# homeboard14.net
KiCad netlist of a schematic drawn in EAGLE
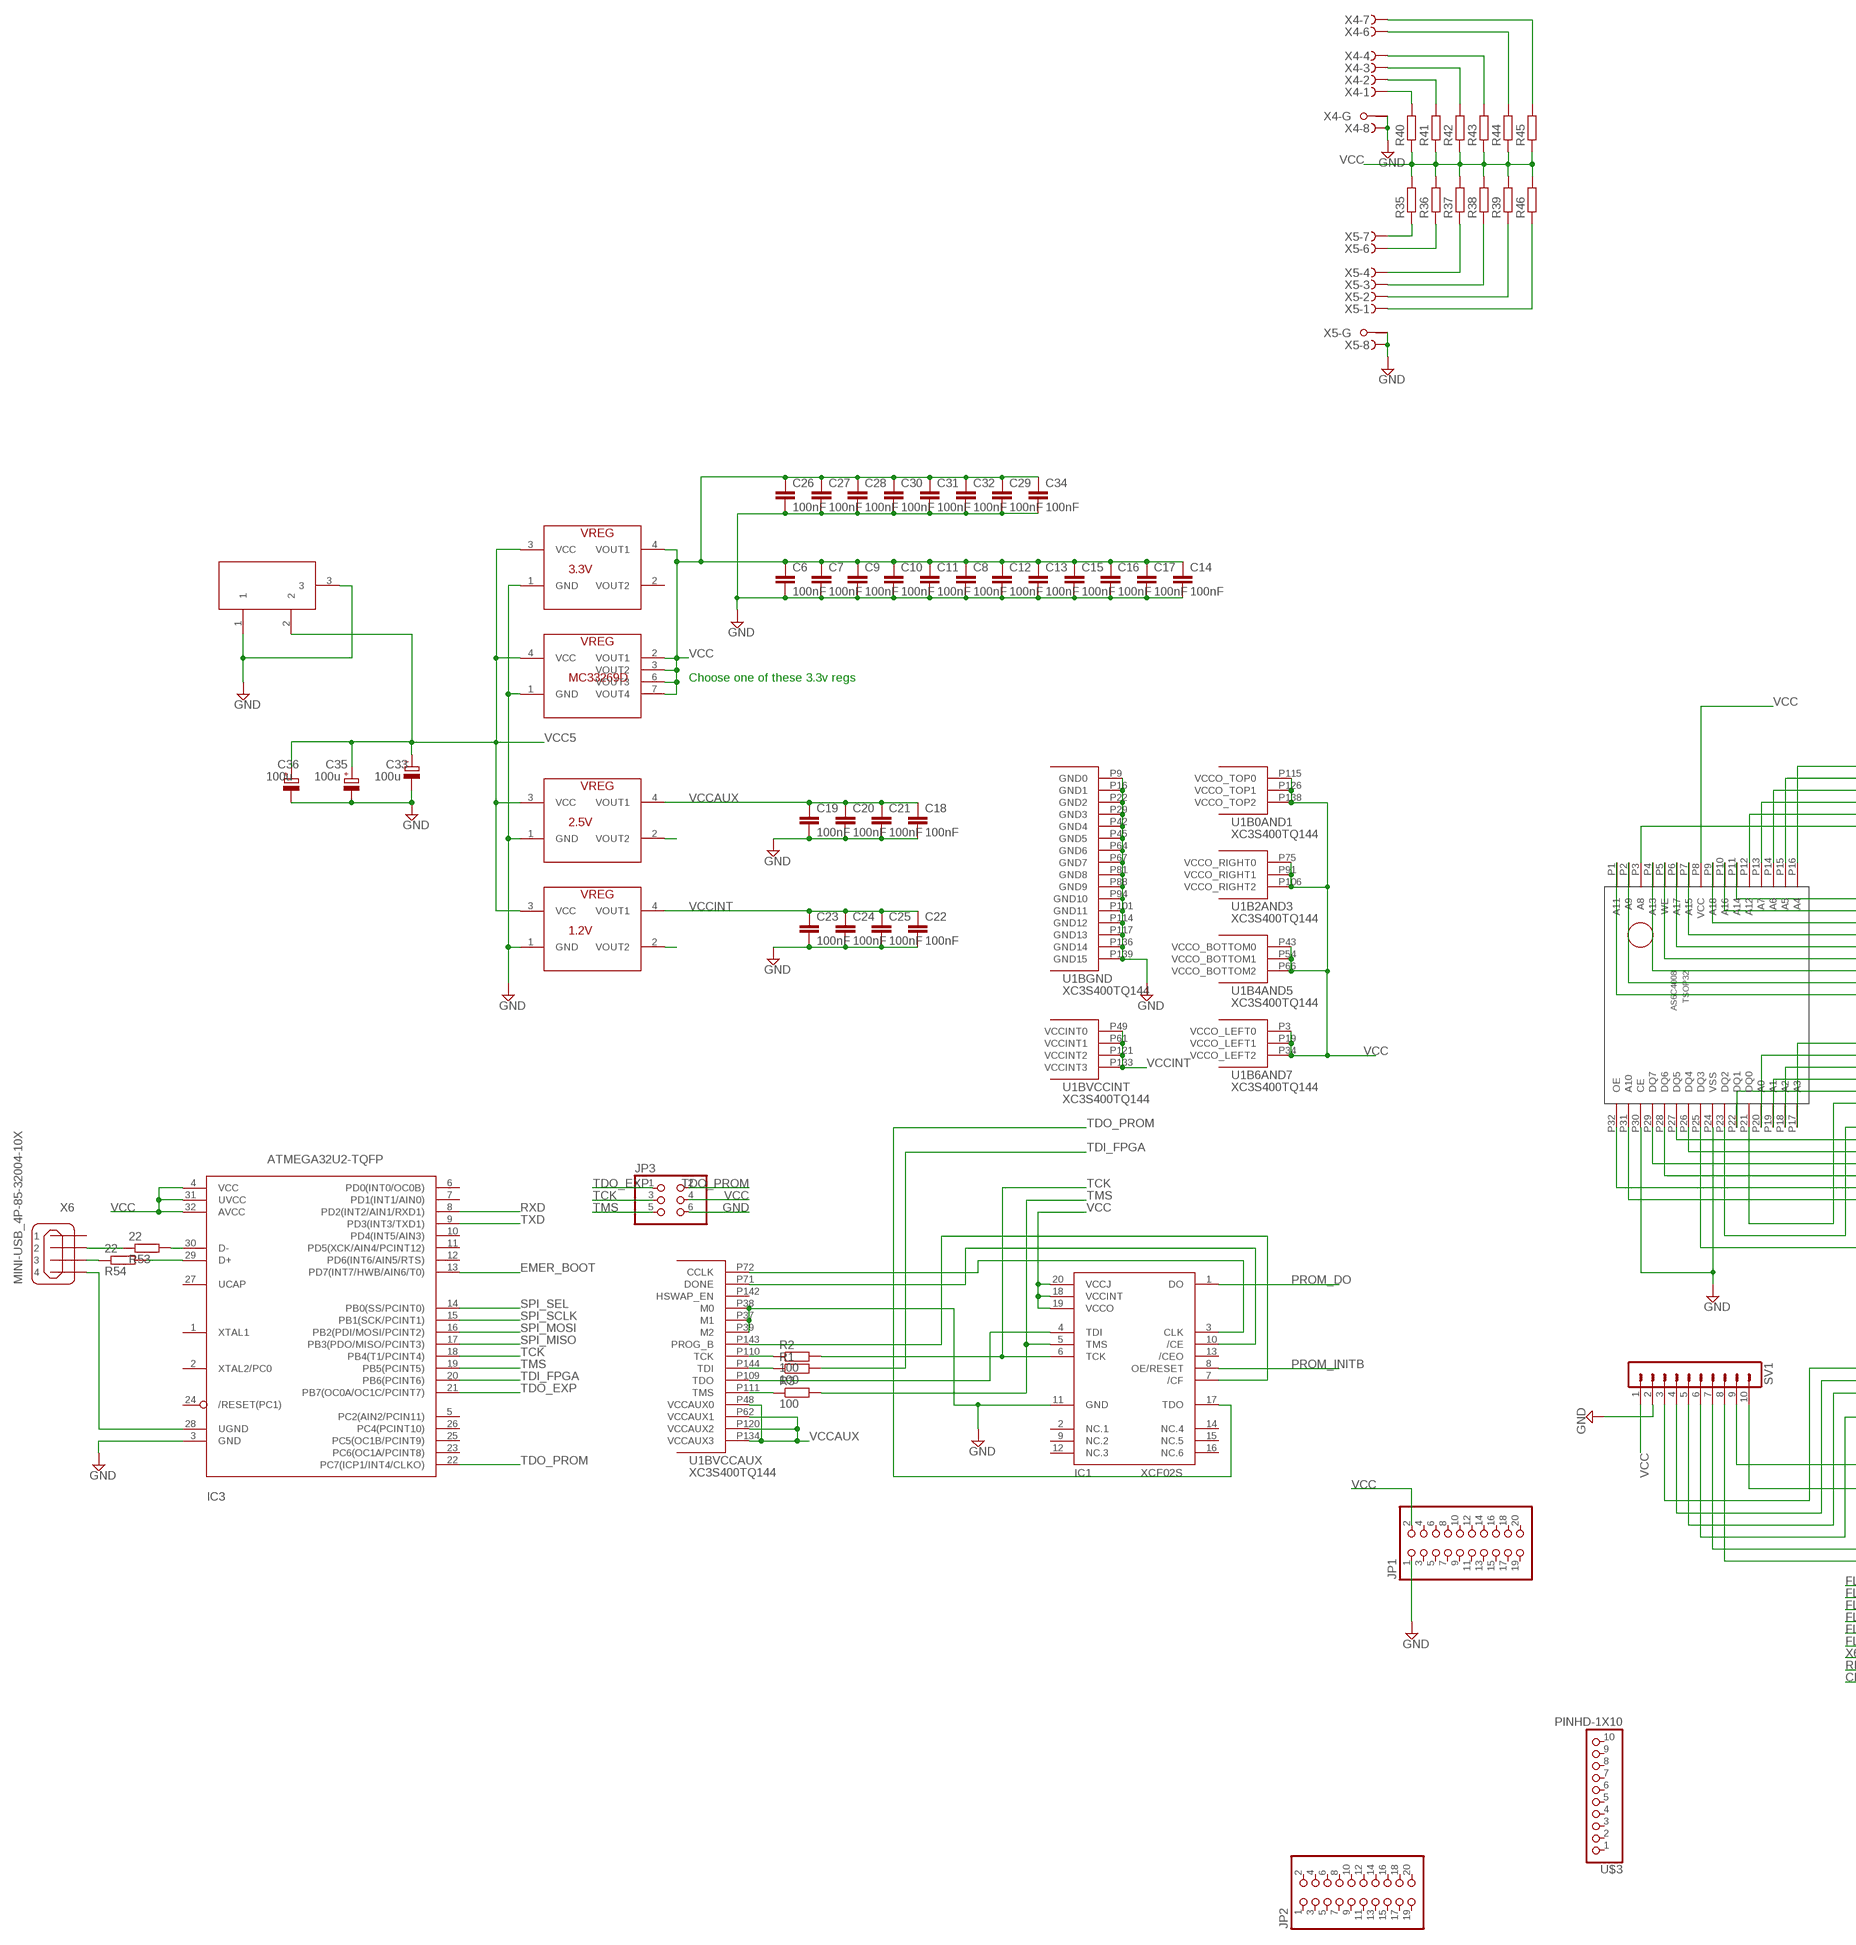
[diagram p0: schematic, sheet 1, part 1 of 3]
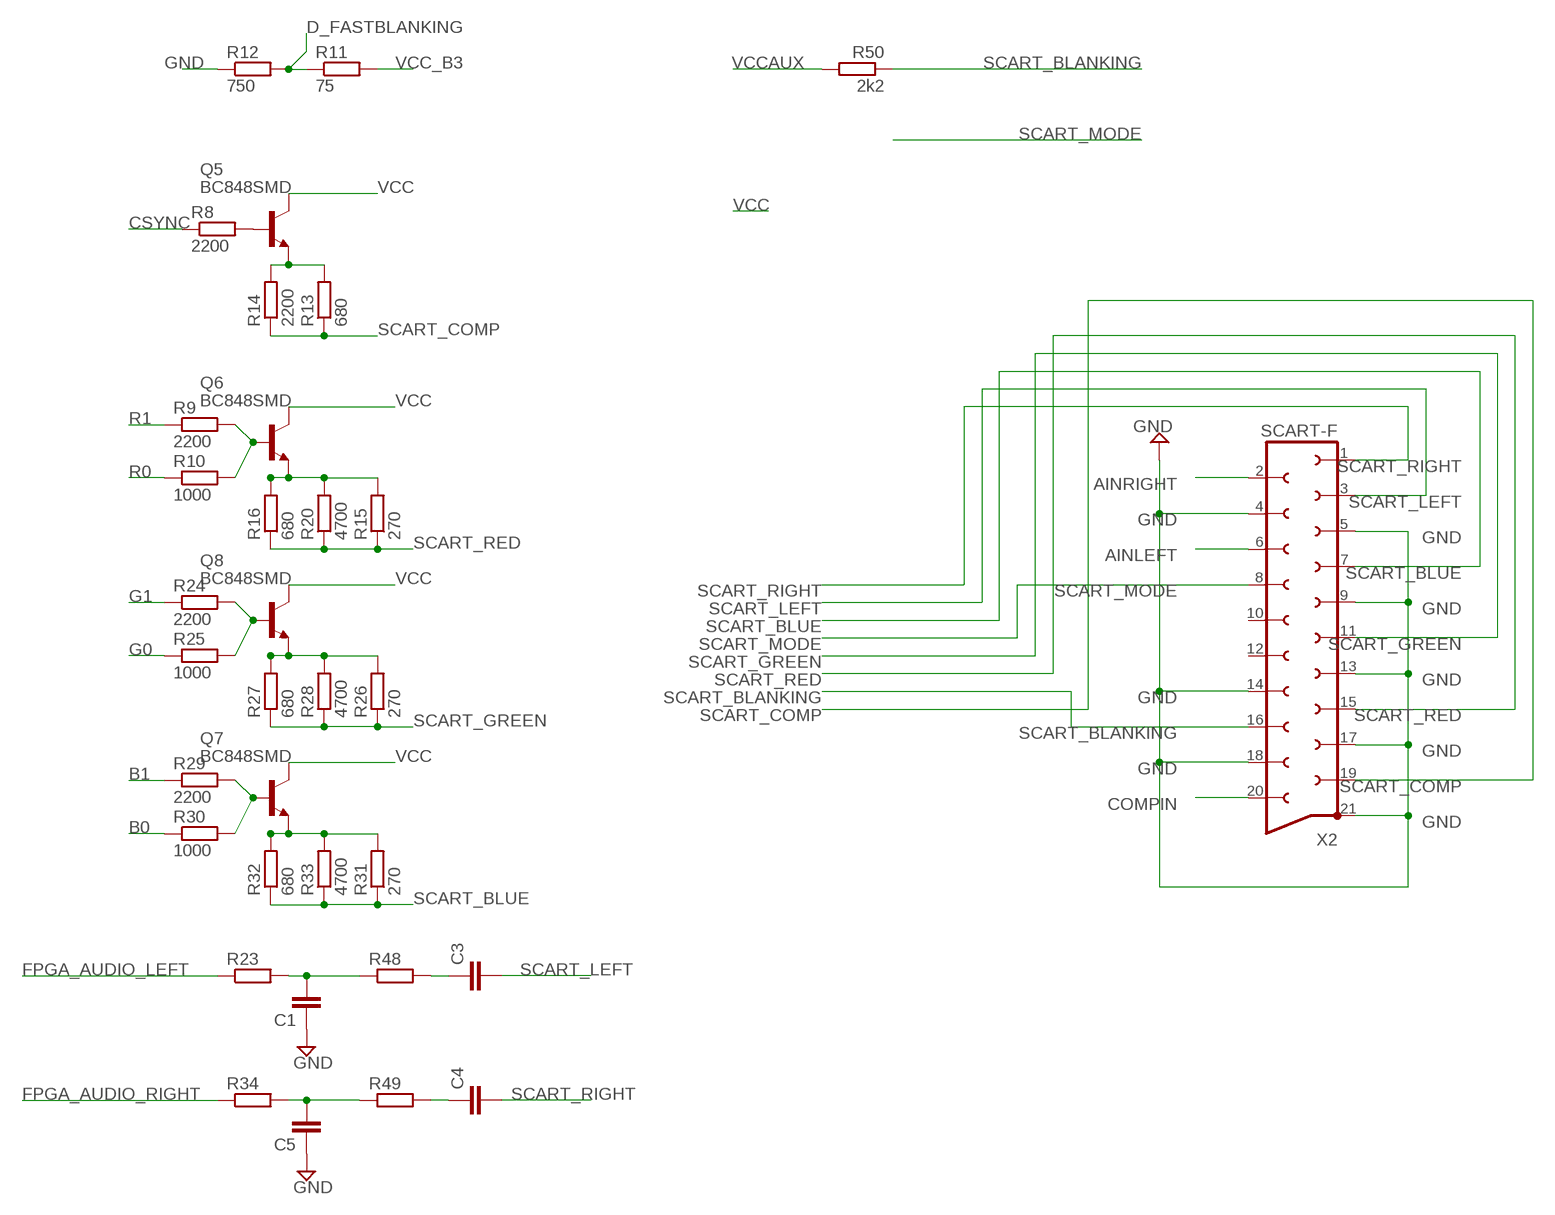
[diagram p1: schematic, sheet 1, part 2 of 3]
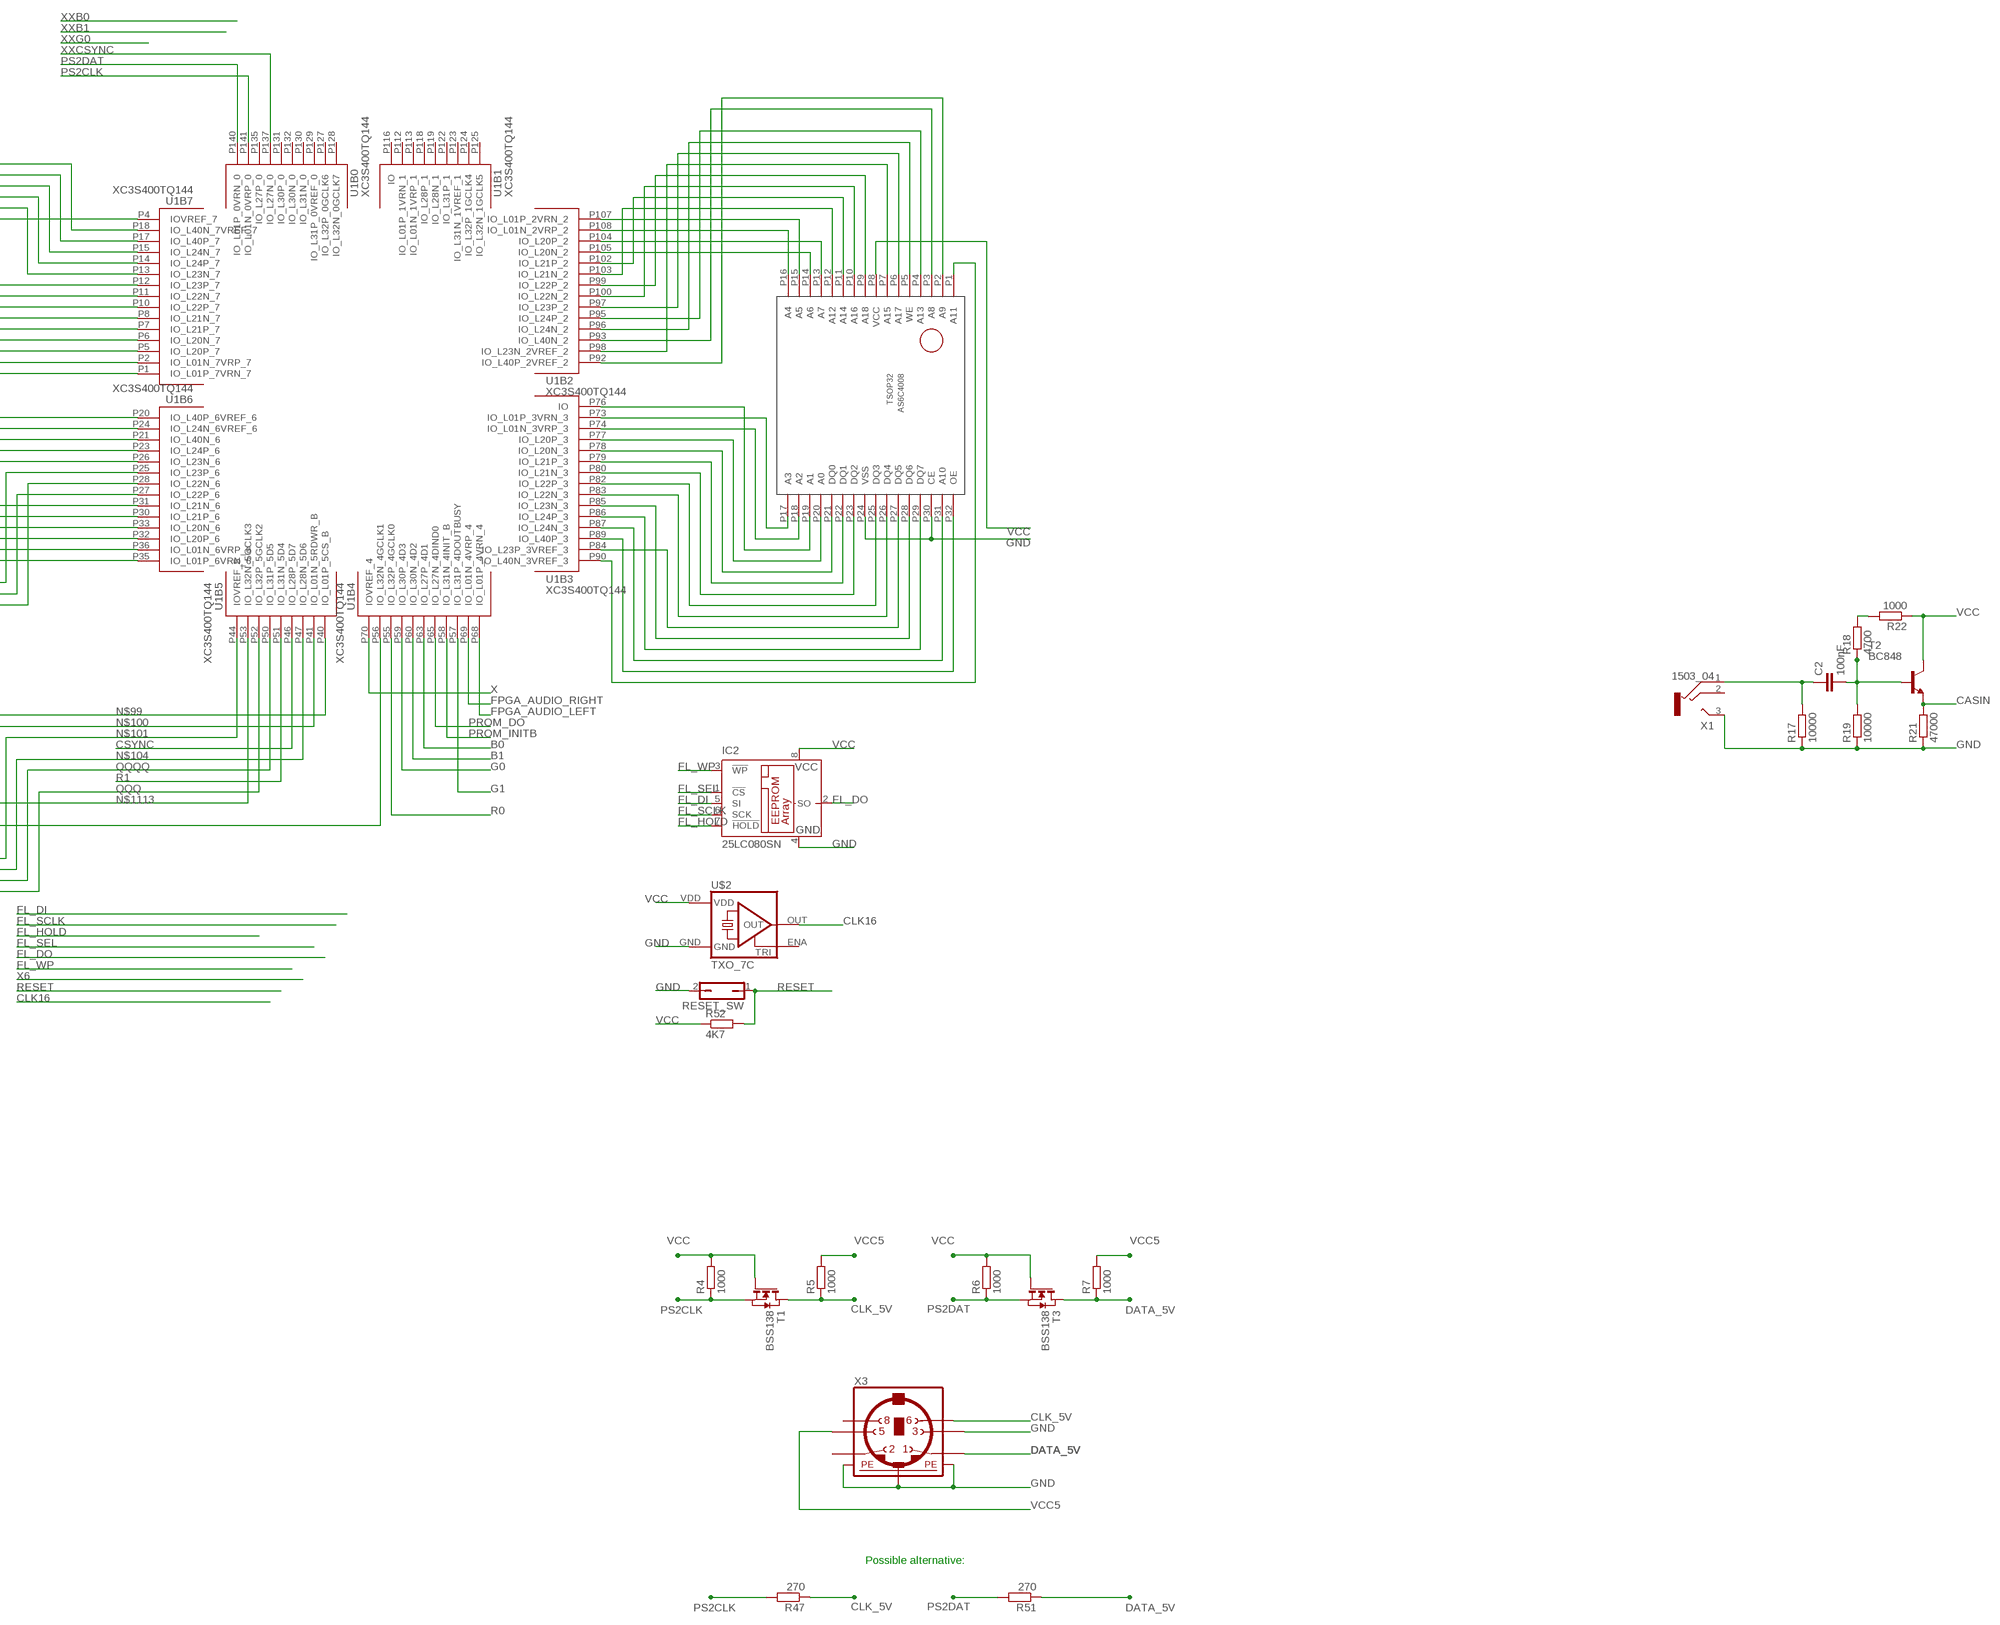
[diagram p2: schematic, sheet 1, part 3 of 3]

(export (version "E")
  (design (tool "Eeschema 10.0.6"))
  (components
    (comp (ref "C1")
      (value "C-EUC0603")
      (footprint "eagle-import:C0603")
      (libsource (lib "eagle-import") (part "resistor_C-EUC0603"))
    )
    (comp (ref "C2")
      (value "100nF")
      (footprint "eagle-import:C0603")
      (libsource (lib "eagle-import") (part "resistor_C-EUC0603"))
    )
    (comp (ref "C3")
      (value "C-EUC0603")
      (footprint "eagle-import:C0603")
      (libsource (lib "eagle-import") (part "resistor_C-EUC0603"))
    )
    (comp (ref "C4")
      (value "C-EUC0603")
      (footprint "eagle-import:C0603")
      (libsource (lib "eagle-import") (part "resistor_C-EUC0603"))
    )
    (comp (ref "C5")
      (value "C-EUC0603")
      (footprint "eagle-import:C0603")
      (libsource (lib "eagle-import") (part "resistor_C-EUC0603"))
    )
    (comp (ref "C6")
      (value "100nF")
      (footprint "eagle-import:C0603")
      (libsource (lib "eagle-import") (part "C-EUC0603"))
    )
    (comp (ref "C7")
      (value "100nF")
      (footprint "eagle-import:C0603")
      (libsource (lib "eagle-import") (part "C-EUC0603"))
    )
    (comp (ref "C8")
      (value "100nF")
      (footprint "eagle-import:C0603")
      (libsource (lib "eagle-import") (part "C-EUC0603"))
    )
    (comp (ref "C9")
      (value "100nF")
      (footprint "eagle-import:C0603")
      (libsource (lib "eagle-import") (part "C-EUC0603"))
    )
    (comp (ref "C10")
      (value "100nF")
      (footprint "eagle-import:C0603")
      (libsource (lib "eagle-import") (part "C-EUC0603"))
    )
    (comp (ref "C11")
      (value "100nF")
      (footprint "eagle-import:C0603")
      (libsource (lib "eagle-import") (part "C-EUC0603"))
    )
    (comp (ref "C12")
      (value "100nF")
      (footprint "eagle-import:C0603")
      (libsource (lib "eagle-import") (part "C-EUC0603"))
    )
    (comp (ref "C13")
      (value "100nF")
      (footprint "eagle-import:C0603")
      (libsource (lib "eagle-import") (part "C-EUC0603"))
    )
    (comp (ref "C14")
      (value "100nF")
      (footprint "eagle-import:C0603")
      (libsource (lib "eagle-import") (part "C-EUC0603"))
    )
    (comp (ref "C15")
      (value "100nF")
      (footprint "eagle-import:C0603")
      (libsource (lib "eagle-import") (part "C-EUC0603"))
    )
    (comp (ref "C16")
      (value "100nF")
      (footprint "eagle-import:C0603")
      (libsource (lib "eagle-import") (part "C-EUC0603"))
    )
    (comp (ref "C17")
      (value "100nF")
      (footprint "eagle-import:C0603")
      (libsource (lib "eagle-import") (part "C-EUC0603"))
    )
    (comp (ref "C18")
      (value "100nF")
      (footprint "eagle-import:C0603")
      (libsource (lib "eagle-import") (part "C-EUC0603"))
    )
    (comp (ref "C19")
      (value "100nF")
      (footprint "eagle-import:C0603")
      (libsource (lib "eagle-import") (part "C-EUC0603"))
    )
    (comp (ref "C20")
      (value "100nF")
      (footprint "eagle-import:C0603")
      (libsource (lib "eagle-import") (part "C-EUC0603"))
    )
    (comp (ref "C21")
      (value "100nF")
      (footprint "eagle-import:C0603")
      (libsource (lib "eagle-import") (part "C-EUC0603"))
    )
    (comp (ref "C22")
      (value "100nF")
      (footprint "eagle-import:C0603")
      (libsource (lib "eagle-import") (part "C-EUC0603"))
    )
    (comp (ref "C23")
      (value "100nF")
      (footprint "eagle-import:C0603")
      (libsource (lib "eagle-import") (part "C-EUC0603"))
    )
    (comp (ref "C24")
      (value "100nF")
      (footprint "eagle-import:C0603")
      (libsource (lib "eagle-import") (part "C-EUC0603"))
    )
    (comp (ref "C25")
      (value "100nF")
      (footprint "eagle-import:C0603")
      (libsource (lib "eagle-import") (part "C-EUC0603"))
    )
    (comp (ref "C26")
      (value "100nF")
      (footprint "eagle-import:C0603")
      (libsource (lib "eagle-import") (part "C-EUC0603"))
    )
    (comp (ref "C27")
      (value "100nF")
      (footprint "eagle-import:C0603")
      (libsource (lib "eagle-import") (part "C-EUC0603"))
    )
    (comp (ref "C28")
      (value "100nF")
      (footprint "eagle-import:C0603")
      (libsource (lib "eagle-import") (part "C-EUC0603"))
    )
    (comp (ref "C29")
      (value "100nF")
      (footprint "eagle-import:C0603")
      (libsource (lib "eagle-import") (part "C-EUC0603"))
    )
    (comp (ref "C30")
      (value "100nF")
      (footprint "eagle-import:C0603")
      (libsource (lib "eagle-import") (part "C-EUC0603"))
    )
    (comp (ref "C31")
      (value "100nF")
      (footprint "eagle-import:C0603")
      (libsource (lib "eagle-import") (part "C-EUC0603"))
    )
    (comp (ref "C32")
      (value "100nF")
      (footprint "eagle-import:C0603")
      (libsource (lib "eagle-import") (part "C-EUC0603"))
    )
    (comp (ref "C33")
      (value "100u")
      (footprint "eagle-import:PANASONIC_D")
      (libsource (lib "eagle-import") (part "CPOL-EUD"))
    )
    (comp (ref "C34")
      (value "100nF")
      (footprint "eagle-import:C0603")
      (libsource (lib "eagle-import") (part "C-EUC0603"))
    )
    (comp (ref "C35")
      (value "100u")
      (footprint "eagle-import:PANASONIC_D")
      (libsource (lib "eagle-import") (part "CPOL-EUD"))
    )
    (comp (ref "C36")
      (value "100u")
      (footprint "eagle-import:PANASONIC_D")
      (libsource (lib "eagle-import") (part "CPOL-EUD"))
    )
    (comp (ref "IC1")
      (value "XCF02S")
      (footprint "eagle-import:VO20")
      (libsource (lib "eagle-import") (part "XCF02S"))
    )
    (comp (ref "IC2")
      (value "25LC080SN")
      (footprint "eagle-import:SO-08")
      (fields (field (name "MF") "MICROCHIP") (field (name "MPN") "25LC080/SN"))
      (libsource (lib "eagle-import") (part "25SNLC080"))
    )
    (comp (ref "IC3")
      (value "ATMEGA32U2-TQFP")
      (footprint "eagle-import:TQFP32-08")
      (libsource (lib "eagle-import") (part "ATMEGA32U2-TQFP"))
    )
    (comp (ref "JP1")
      (value "PINHD-2X10")
      (footprint "eagle-import:2X10")
      (libsource (lib "eagle-import") (part "PINHD-2X10"))
    )
    (comp (ref "JP2")
      (value "PINHD-2X10")
      (footprint "eagle-import:2X10")
      (libsource (lib "eagle-import") (part "PINHD-2X10"))
    )
    (comp (ref "JP3")
      (value "PINHD-2X3")
      (footprint "eagle-import:2X03")
      (libsource (lib "eagle-import") (part "PINHD-2X3"))
    )
    (comp (ref "Q5")
      (value "BC848SMD")
      (footprint "eagle-import:SOT23")
      (libsource (lib "eagle-import") (part "BC848SMD"))
    )
    (comp (ref "Q6")
      (value "BC848SMD")
      (footprint "eagle-import:SOT23")
      (libsource (lib "eagle-import") (part "BC848SMD"))
    )
    (comp (ref "Q7")
      (value "BC848SMD")
      (footprint "eagle-import:SOT23")
      (libsource (lib "eagle-import") (part "BC848SMD"))
    )
    (comp (ref "Q8")
      (value "BC848SMD")
      (footprint "eagle-import:SOT23")
      (libsource (lib "eagle-import") (part "BC848SMD"))
    )
    (comp (ref "R1")
      (value "100")
      (footprint "eagle-import:R0805")
      (libsource (lib "eagle-import") (part "R-EU_R0805"))
    )
    (comp (ref "R2")
      (value "100")
      (footprint "eagle-import:R0805")
      (libsource (lib "eagle-import") (part "R-EU_R0805"))
    )
    (comp (ref "R3")
      (value "100")
      (footprint "eagle-import:R0805")
      (libsource (lib "eagle-import") (part "R-EU_R0805"))
    )
    (comp (ref "R4")
      (value "1000")
      (footprint "eagle-import:R0805")
      (libsource (lib "eagle-import") (part "R-EU_R0805"))
    )
    (comp (ref "R5")
      (value "1000")
      (footprint "eagle-import:R0805")
      (libsource (lib "eagle-import") (part "R-EU_R0805"))
    )
    (comp (ref "R6")
      (value "1000")
      (footprint "eagle-import:R0805")
      (libsource (lib "eagle-import") (part "R-EU_R0805"))
    )
    (comp (ref "R7")
      (value "1000")
      (footprint "eagle-import:R0805")
      (libsource (lib "eagle-import") (part "R-EU_R0805"))
    )
    (comp (ref "R8")
      (value "2200")
      (footprint "eagle-import:R0805")
      (libsource (lib "eagle-import") (part "R-EU_R0805"))
    )
    (comp (ref "R9")
      (value "2200")
      (footprint "eagle-import:R0805")
      (libsource (lib "eagle-import") (part "R-EU_R0805"))
    )
    (comp (ref "R10")
      (value "1000")
      (footprint "eagle-import:R0805")
      (libsource (lib "eagle-import") (part "R-EU_R0805"))
    )
    (comp (ref "R11")
      (value "75")
      (footprint "eagle-import:R0805")
      (libsource (lib "eagle-import") (part "R-EU_R0805"))
    )
    (comp (ref "R12")
      (value "750")
      (footprint "eagle-import:R0805")
      (libsource (lib "eagle-import") (part "R-EU_R0805"))
    )
    (comp (ref "R13")
      (value "680")
      (footprint "eagle-import:R0805")
      (libsource (lib "eagle-import") (part "R-EU_R0805"))
    )
    (comp (ref "R14")
      (value "2200")
      (footprint "eagle-import:R0805")
      (libsource (lib "eagle-import") (part "R-EU_R0805"))
    )
    (comp (ref "R15")
      (value "270")
      (footprint "eagle-import:R0805")
      (libsource (lib "eagle-import") (part "R-EU_R0805"))
    )
    (comp (ref "R16")
      (value "680")
      (footprint "eagle-import:R0805")
      (libsource (lib "eagle-import") (part "R-EU_R0805"))
    )
    (comp (ref "R17")
      (value "10000")
      (footprint "eagle-import:R0805")
      (libsource (lib "eagle-import") (part "R-EU_R0805"))
    )
    (comp (ref "R18")
      (value "4700")
      (footprint "eagle-import:R0805")
      (libsource (lib "eagle-import") (part "R-EU_R0805"))
    )
    (comp (ref "R19")
      (value "10000")
      (footprint "eagle-import:R0805")
      (libsource (lib "eagle-import") (part "R-EU_R0805"))
    )
    (comp (ref "R20")
      (value "4700")
      (footprint "eagle-import:R0805")
      (libsource (lib "eagle-import") (part "R-EU_R0805"))
    )
    (comp (ref "R21")
      (value "47000")
      (footprint "eagle-import:R0805")
      (libsource (lib "eagle-import") (part "R-EU_R0805"))
    )
    (comp (ref "R22")
      (value "1000")
      (footprint "eagle-import:R0805")
      (libsource (lib "eagle-import") (part "R-EU_R0805"))
    )
    (comp (ref "R23")
      (value "R-EU_M0805")
      (footprint "eagle-import:M0805")
      (libsource (lib "eagle-import") (part "resistor_R-EU_M0805"))
    )
    (comp (ref "R24")
      (value "2200")
      (footprint "eagle-import:R0805")
      (libsource (lib "eagle-import") (part "R-EU_R0805"))
    )
    (comp (ref "R25")
      (value "1000")
      (footprint "eagle-import:R0805")
      (libsource (lib "eagle-import") (part "R-EU_R0805"))
    )
    (comp (ref "R26")
      (value "270")
      (footprint "eagle-import:R0805")
      (libsource (lib "eagle-import") (part "R-EU_R0805"))
    )
    (comp (ref "R27")
      (value "680")
      (footprint "eagle-import:R0805")
      (libsource (lib "eagle-import") (part "R-EU_R0805"))
    )
    (comp (ref "R28")
      (value "4700")
      (footprint "eagle-import:R0805")
      (libsource (lib "eagle-import") (part "R-EU_R0805"))
    )
    (comp (ref "R29")
      (value "2200")
      (footprint "eagle-import:R0805")
      (libsource (lib "eagle-import") (part "R-EU_R0805"))
    )
    (comp (ref "R30")
      (value "1000")
      (footprint "eagle-import:R0805")
      (libsource (lib "eagle-import") (part "R-EU_R0805"))
    )
    (comp (ref "R31")
      (value "270")
      (footprint "eagle-import:R0805")
      (libsource (lib "eagle-import") (part "R-EU_R0805"))
    )
    (comp (ref "R32")
      (value "680")
      (footprint "eagle-import:R0805")
      (libsource (lib "eagle-import") (part "R-EU_R0805"))
    )
    (comp (ref "R33")
      (value "4700")
      (footprint "eagle-import:R0805")
      (libsource (lib "eagle-import") (part "R-EU_R0805"))
    )
    (comp (ref "R34")
      (value "R-EU_M0805")
      (footprint "eagle-import:M0805")
      (libsource (lib "eagle-import") (part "resistor_R-EU_M0805"))
    )
    (comp (ref "R35")
      (value "R-EU_M0805")
      (footprint "eagle-import:M0805")
      (libsource (lib "eagle-import") (part "resistor_R-EU_M0805"))
    )
    (comp (ref "R36")
      (value "R-EU_M0805")
      (footprint "eagle-import:M0805")
      (libsource (lib "eagle-import") (part "resistor_R-EU_M0805"))
    )
    (comp (ref "R37")
      (value "R-EU_M0805")
      (footprint "eagle-import:M0805")
      (libsource (lib "eagle-import") (part "resistor_R-EU_M0805"))
    )
    (comp (ref "R38")
      (value "R-EU_M0805")
      (footprint "eagle-import:M0805")
      (libsource (lib "eagle-import") (part "resistor_R-EU_M0805"))
    )
    (comp (ref "R39")
      (value "R-EU_M0805")
      (footprint "eagle-import:M0805")
      (libsource (lib "eagle-import") (part "resistor_R-EU_M0805"))
    )
    (comp (ref "R40")
      (value "R-EU_M0805")
      (footprint "eagle-import:M0805")
      (libsource (lib "eagle-import") (part "resistor_R-EU_M0805"))
    )
    (comp (ref "R41")
      (value "R-EU_M0805")
      (footprint "eagle-import:M0805")
      (libsource (lib "eagle-import") (part "resistor_R-EU_M0805"))
    )
    (comp (ref "R42")
      (value "R-EU_M0805")
      (footprint "eagle-import:M0805")
      (libsource (lib "eagle-import") (part "resistor_R-EU_M0805"))
    )
    (comp (ref "R43")
      (value "R-EU_M0805")
      (footprint "eagle-import:M0805")
      (libsource (lib "eagle-import") (part "resistor_R-EU_M0805"))
    )
    (comp (ref "R44")
      (value "R-EU_M0805")
      (footprint "eagle-import:M0805")
      (libsource (lib "eagle-import") (part "resistor_R-EU_M0805"))
    )
    (comp (ref "R45")
      (value "R-EU_M0805")
      (footprint "eagle-import:M0805")
      (libsource (lib "eagle-import") (part "resistor_R-EU_M0805"))
    )
    (comp (ref "R46")
      (value "R-EU_M0805")
      (footprint "eagle-import:M0805")
      (libsource (lib "eagle-import") (part "resistor_R-EU_M0805"))
    )
    (comp (ref "R47")
      (value "270")
      (footprint "eagle-import:R0805")
      (libsource (lib "eagle-import") (part "R-EU_R0805"))
    )
    (comp (ref "R48")
      (value "R-EU_M0805")
      (footprint "eagle-import:M0805")
      (libsource (lib "eagle-import") (part "resistor_R-EU_M0805"))
    )
    (comp (ref "R49")
      (value "R-EU_M0805")
      (footprint "eagle-import:M0805")
      (libsource (lib "eagle-import") (part "resistor_R-EU_M0805"))
    )
    (comp (ref "R50")
      (value "2k2")
      (footprint "eagle-import:M0805")
      (libsource (lib "eagle-import") (part "resistor_R-EU_M0805"))
    )
    (comp (ref "R51")
      (value "270")
      (footprint "eagle-import:R0805")
      (libsource (lib "eagle-import") (part "R-EU_R0805"))
    )
    (comp (ref "R52")
      (value "4K7")
      (footprint "eagle-import:M0805")
      (libsource (lib "eagle-import") (part "resistor_R-EU_M0805"))
    )
    (comp (ref "R53")
      (value "22")
      (footprint "eagle-import:R0805")
      (libsource (lib "eagle-import") (part "R-EU_R0805"))
    )
    (comp (ref "R54")
      (value "22")
      (footprint "eagle-import:R0805")
      (libsource (lib "eagle-import") (part "R-EU_R0805"))
    )
    (comp (ref "REG1.2")
      (value "1.2V")
      (footprint "eagle-import:SOT223")
      (libsource (lib "eagle-import") (part "NX1117"))
    )
    (comp (ref "REG2.5")
      (value "2.5V")
      (footprint "eagle-import:SOT223")
      (libsource (lib "eagle-import") (part "NX1117"))
    )
    (comp (ref "RESET_SW")
      (value "JP1Q")
      (footprint "eagle-import:JP1")
      (libsource (lib "eagle-import") (part "JP1Q"))
    )
    (comp (ref "SV1")
      (value "MA10-1")
      (footprint "eagle-import:MA10-1")
      (libsource (lib "eagle-import") (part "MA10-1"))
    )
    (comp (ref "T1")
      (value "BSS138")
      (footprint "eagle-import:SOT-23")
      (libsource (lib "eagle-import") (part "NMOSSOT23"))
    )
    (comp (ref "T2")
      (value "BC848")
      (footprint "eagle-import:SOT23")
      (libsource (lib "eagle-import") (part "BC848"))
    )
    (comp (ref "T3")
      (value "BSS138")
      (footprint "eagle-import:SOT-23")
      (libsource (lib "eagle-import") (part "NMOSSOT23"))
    )
    (comp (ref "U$1")
      (value "AS6C4008")
      (footprint "eagle-import:TSOP32")
      (libsource (lib "eagle-import") (part "AS6C4008"))
    )
    (comp (ref "U$2")
      (value "TXO_7C")
      (footprint "eagle-import:OSC_7C")
      (libsource (lib "eagle-import") (part "TXO_7C"))
    )
    (comp (ref "U$3")
      (value "PINHD-1X10")
      (footprint "eagle-import:1X10-BIG")
      (libsource (lib "eagle-import") (part "PINHD-1X10"))
    )
    (comp (ref "U$4")
      (value "3.3V")
      (footprint "eagle-import:SOT223")
      (libsource (lib "eagle-import") (part "NX1117"))
    )
    (comp (ref "U$5")
      (value "MC33269D")
      (footprint "eagle-import:SO8")
      (libsource (lib "eagle-import") (part "MC33269D"))
    )
    (comp (ref "U$6")
      (value "AS6C4008")
      (footprint "eagle-import:TSOP32")
      (libsource (lib "eagle-import") (part "AS6C4008"))
    )
    (comp (ref "U1")
      (value "XC3S400TQ144")
      (footprint "eagle-import:TQ144")
      (libsource (lib "eagle-import") (part "XC3S400TQ144"))
    )
    (comp (ref "X1")
      (value "1503_04")
      (footprint "eagle-import:1503_04")
      (libsource (lib "eagle-import") (part "1503_04"))
    )
    (comp (ref "X2")
      (value "SCART-F")
      (footprint "eagle-import:SCART-F")
      (libsource (lib "eagle-import") (part "SCART-F"))
    )
    (comp (ref "X3")
      (value "MINI_DIN_6")
      (footprint "eagle-import:M_DIN6")
      (libsource (lib "eagle-import") (part "MINI_DIN_6"))
    )
    (comp (ref "X4")
      (value "F09HPS")
      (footprint "eagle-import:F09HP")
      (libsource (lib "eagle-import") (part "F09HPS"))
    )
    (comp (ref "X5")
      (value "F09HPS")
      (footprint "eagle-import:F09HP")
      (libsource (lib "eagle-import") (part "F09HPS"))
    )
    (comp (ref "X6")
      (value "MINI-USB_4P-85-32004-10X")
      (footprint "eagle-import:85-32004-10X")
      (libsource (lib "eagle-import") (part "MINI-USB_4P-85-32004-10X"))
    )
    (comp (ref "X8")
      (value "DC21MMX")
      (footprint "eagle-import:DC-21MM")
      (libsource (lib "eagle-import") (part "DC21MMX"))
    )
  )
  (nets
    (net (code "1") (name "/AINLEFT") (class "Default")
      (node (ref "X2") (pin "6") (pinfunction "6_6") (pintype "passive"))
    )
    (net (code "2") (name "/AINRIGHT") (class "Default")
      (node (ref "X2") (pin "2") (pinfunction "2_2") (pintype "passive"))
    )
    (net (code "3") (name "/B0") (class "Default")
      (node (ref "R30") (pin "1") (pinfunction "1_1") (pintype "passive"))
      (node (ref "U1") (pin "P63") (pinfunction "IO_L27P_4D1_P63") (pintype "bidirectional"))
    )
    (net (code "4") (name "/B1") (class "Default")
      (node (ref "R29") (pin "1") (pinfunction "1_1") (pintype "passive"))
      (node (ref "U1") (pin "P60") (pinfunction "IO_L30N_4D2_P60") (pintype "bidirectional"))
    )
    (net (code "5") (name "/CASIN") (class "Default")
      (node (ref "R21") (pin "2") (pinfunction "2_2") (pintype "passive"))
      (node (ref "T2") (pin "2") (pinfunction "E_2") (pintype "passive"))
    )
    (net (code "6") (name "/CLK16") (class "Default")
      (node (ref "U$2") (pin "OUT") (pinfunction "OUT_OUT") (pintype "output"))
    )
    (net (code "7") (name "/CLK_5V") (class "Default")
      (node (ref "R47") (pin "1") (pinfunction "1_1") (pintype "passive"))
      (node (ref "R5") (pin "1") (pinfunction "1_1") (pintype "passive"))
      (node (ref "T1") (pin "1") (pinfunction "D_1") (pintype "passive"))
      (node (ref "X3") (pin "6") (pinfunction "6_6") (pintype "passive"))
    )
    (net (code "8") (name "/COMPIN") (class "Default")
      (node (ref "X2") (pin "20") (pinfunction "20_20") (pintype "passive"))
    )
    (net (code "9") (name "/CSYNC") (class "Default")
      (node (ref "R8") (pin "1") (pinfunction "1_1") (pintype "passive"))
      (node (ref "U1") (pin "P46") (pinfunction "IO_L28P_5D7_P46") (pintype "bidirectional"))
    )
    (net (code "10") (name "/DATA_5V") (class "Default")
      (node (ref "R51") (pin "1") (pinfunction "1_1") (pintype "passive"))
      (node (ref "R7") (pin "1") (pinfunction "1_1") (pintype "passive"))
      (node (ref "T3") (pin "1") (pinfunction "D_1") (pintype "passive"))
      (node (ref "X3") (pin "1") (pinfunction "1_1") (pintype "passive"))
    )
    (net (code "11") (name "/D_FASTBLANKING") (class "Default")
      (node (ref "R11") (pin "1") (pinfunction "1_1") (pintype "passive"))
      (node (ref "R12") (pin "2") (pinfunction "2_2") (pintype "passive"))
    )
    (net (code "12") (name "/EMER_BOOT") (class "Default")
      (node (ref "IC3") (pin "13") (pinfunction "PD7(INT7/HWB/AIN6/T0)_13") (pintype "bidirectional"))
    )
    (net (code "13") (name "/FL_DI") (class "Default")
      (node (ref "IC2") (pin "5") (pinfunction "SI_5") (pintype "input"))
    )
    (net (code "14") (name "/FL_DO") (class "Default")
      (node (ref "IC2") (pin "2") (pinfunction "SO_2") (pintype "bidirectional"))
    )
    (net (code "15") (name "/FL_HOLD") (class "Default")
      (node (ref "IC2") (pin "7") (pinfunction "~{HOLD}_7") (pintype "input"))
    )
    (net (code "16") (name "/FL_SCLK") (class "Default")
      (node (ref "IC2") (pin "6") (pinfunction "SCK_6") (pintype "input"))
    )
    (net (code "17") (name "/FL_SEL") (class "Default")
      (node (ref "IC2") (pin "1") (pinfunction "~{CS}_1") (pintype "input"))
    )
    (net (code "18") (name "/FL_WP") (class "Default")
      (node (ref "IC2") (pin "3") (pinfunction "~{WP}_3") (pintype "input"))
    )
    (net (code "19") (name "/FPGA_AUDIO_LEFT") (class "Default")
      (node (ref "R23") (pin "1") (pinfunction "1_1") (pintype "passive"))
      (node (ref "U1") (pin "P68") (pinfunction "IO_L01P_4VRN_4_P68") (pintype "bidirectional"))
    )
    (net (code "20") (name "/FPGA_AUDIO_RIGHT") (class "Default")
      (node (ref "R34") (pin "1") (pinfunction "1_1") (pintype "passive"))
      (node (ref "U1") (pin "P69") (pinfunction "IO_L01N_4VRP_4_P69") (pintype "bidirectional"))
    )
    (net (code "21") (name "/G0") (class "Default")
      (node (ref "R25") (pin "1") (pinfunction "1_1") (pintype "passive"))
      (node (ref "U1") (pin "P59") (pinfunction "IO_L30P_4D3_P59") (pintype "bidirectional"))
    )
    (net (code "22") (name "/G1") (class "Default")
      (node (ref "R24") (pin "1") (pinfunction "1_1") (pintype "passive"))
      (node (ref "U1") (pin "P57") (pinfunction "IO_L31P_4DOUTBUSY_P57") (pintype "bidirectional"))
    )
    (net (code "23") (name "/N$99") (class "Default")
      (node (ref "SV1") (pin "3") (pinfunction "3_3") (pintype "passive"))
      (node (ref "U1") (pin "P40") (pinfunction "IO_L01P_5CS_B_P40") (pintype "bidirectional"))
    )
    (net (code "24") (name "/N$100") (class "Default")
      (node (ref "SV1") (pin "4") (pinfunction "4_4") (pintype "passive"))
      (node (ref "U1") (pin "P41") (pinfunction "IO_L01N_5RDWR_B_P41") (pintype "bidirectional"))
    )
    (net (code "25") (name "/N$101") (class "Default")
      (node (ref "SV1") (pin "5") (pinfunction "5_5") (pintype "passive"))
      (node (ref "U1") (pin "P44") (pinfunction "IOVREF_5_P44") (pintype "bidirectional"))
    )
    (net (code "26") (name "/N$104") (class "Default")
      (node (ref "SV1") (pin "6") (pinfunction "6_6") (pintype "passive"))
      (node (ref "U1") (pin "P47") (pinfunction "IO_L28N_5D6_P47") (pintype "bidirectional"))
    )
    (net (code "27") (name "/N$1113") (class "Default")
      (node (ref "SV1") (pin "9") (pinfunction "9_9") (pintype "passive"))
      (node (ref "U1") (pin "P53") (pinfunction "IO_L32N_5GCLK3_P53") (pintype "bidirectional"))
    )
    (net (code "28") (name "/PROM_DO") (class "Default")
      (node (ref "IC1") (pin "1") (pinfunction "DO_1") (pintype "bidirectional"))
      (node (ref "U1") (pin "P65") (pinfunction "IO_L27N_4DIND0_P65") (pintype "bidirectional"))
    )
    (net (code "29") (name "/PROM_INITB") (class "Default")
      (node (ref "IC1") (pin "8") (pinfunction "OE/RESET_8") (pintype "bidirectional"))
      (node (ref "U1") (pin "P58") (pinfunction "IO_L31N_4INIT_B_P58") (pintype "bidirectional"))
    )
    (net (code "30") (name "/PS2CLK") (class "Default")
      (node (ref "R4") (pin "1") (pinfunction "1_1") (pintype "passive"))
      (node (ref "R47") (pin "2") (pinfunction "2_2") (pintype "passive"))
      (node (ref "T1") (pin "2") (pinfunction "S_2") (pintype "passive"))
      (node (ref "U1") (pin "P141") (pinfunction "IO_L01N_0VRP_0_P141") (pintype "bidirectional"))
    )
    (net (code "31") (name "/PS2DAT") (class "Default")
      (node (ref "R51") (pin "2") (pinfunction "2_2") (pintype "passive"))
      (node (ref "R6") (pin "1") (pinfunction "1_1") (pintype "passive"))
      (node (ref "T3") (pin "2") (pinfunction "S_2") (pintype "passive"))
      (node (ref "U1") (pin "P140") (pinfunction "IO_L01P_0VRN_0_P140") (pintype "bidirectional"))
    )
    (net (code "32") (name "/QQQ") (class "Default")
      (node (ref "SV1") (pin "8") (pinfunction "8_8") (pintype "passive"))
      (node (ref "U1") (pin "P52") (pinfunction "IO_L32P_5GCLK2_P52") (pintype "bidirectional"))
    )
    (net (code "33") (name "/QQQQ") (class "Default")
      (node (ref "SV1") (pin "7") (pinfunction "7_7") (pintype "passive"))
      (node (ref "U1") (pin "P50") (pinfunction "IO_L31P_5D5_P50") (pintype "bidirectional"))
    )
    (net (code "34") (name "/R0") (class "Default")
      (node (ref "R10") (pin "1") (pinfunction "1_1") (pintype "passive"))
      (node (ref "U1") (pin "P55") (pinfunction "IO_L32P_4GCLK0_P55") (pintype "bidirectional"))
    )
    (net (code "35") (name "/R1") (class "Default")
      (node (ref "R9") (pin "1") (pinfunction "1_1") (pintype "passive"))
      (node (ref "U1") (pin "P51") (pinfunction "IO_L31N_5D4_P51") (pintype "bidirectional"))
    )
    (net (code "36") (name "/RESET") (class "Default")
      (node (ref "R52") (pin "2") (pinfunction "2_2") (pintype "passive"))
      (node (ref "RESET_SW") (pin "1") (pinfunction "1_1") (pintype "passive"))
    )
    (net (code "37") (name "/RXD") (class "Default")
      (node (ref "IC3") (pin "8") (pinfunction "PD2(INT2/AIN1/RXD1)_8") (pintype "bidirectional"))
    )
    (net (code "38") (name "/SCART_BLANKING") (class "Default")
      (node (ref "R50") (pin "1") (pinfunction "1_1") (pintype "passive"))
      (node (ref "X2") (pin "16") (pinfunction "16_16") (pintype "passive"))
    )
    (net (code "39") (name "/SCART_BLUE") (class "Default")
      (node (ref "R31") (pin "1") (pinfunction "1_1") (pintype "passive"))
      (node (ref "R32") (pin "1") (pinfunction "1_1") (pintype "passive"))
      (node (ref "R33") (pin "1") (pinfunction "1_1") (pintype "passive"))
      (node (ref "X2") (pin "7") (pinfunction "7_7") (pintype "passive"))
    )
    (net (code "40") (name "/SCART_COMP") (class "Default")
      (node (ref "R13") (pin "1") (pinfunction "1_1") (pintype "passive"))
      (node (ref "R14") (pin "1") (pinfunction "1_1") (pintype "passive"))
      (node (ref "X2") (pin "19") (pinfunction "19_19") (pintype "passive"))
    )
    (net (code "41") (name "/SCART_GREEN") (class "Default")
      (node (ref "R26") (pin "1") (pinfunction "1_1") (pintype "passive"))
      (node (ref "R27") (pin "1") (pinfunction "1_1") (pintype "passive"))
      (node (ref "R28") (pin "1") (pinfunction "1_1") (pintype "passive"))
      (node (ref "X2") (pin "11") (pinfunction "11_11") (pintype "passive"))
    )
    (net (code "42") (name "/SCART_LEFT") (class "Default")
      (node (ref "C3") (pin "2") (pinfunction "2_2") (pintype "passive"))
      (node (ref "X2") (pin "3") (pinfunction "3_3") (pintype "passive"))
    )
    (net (code "43") (name "/SCART_MODE") (class "Default")
      (node (ref "X2") (pin "8") (pinfunction "8_8") (pintype "passive"))
    )
    (net (code "44") (name "/SCART_RED") (class "Default")
      (node (ref "R15") (pin "1") (pinfunction "1_1") (pintype "passive"))
      (node (ref "R16") (pin "1") (pinfunction "1_1") (pintype "passive"))
      (node (ref "R20") (pin "1") (pinfunction "1_1") (pintype "passive"))
      (node (ref "X2") (pin "15") (pinfunction "15_15") (pintype "passive"))
    )
    (net (code "45") (name "/SCART_RIGHT") (class "Default")
      (node (ref "C4") (pin "2") (pinfunction "2_2") (pintype "passive"))
      (node (ref "X2") (pin "1") (pinfunction "1_1") (pintype "passive"))
    )
    (net (code "46") (name "/SPI_MISO") (class "Default")
      (node (ref "IC3") (pin "17") (pinfunction "PB3(PDO/MISO/PCINT3)_17") (pintype "bidirectional"))
    )
    (net (code "47") (name "/SPI_MOSI") (class "Default")
      (node (ref "IC3") (pin "16") (pinfunction "PB2(PDI/MOSI/PCINT2)_16") (pintype "bidirectional"))
    )
    (net (code "48") (name "/SPI_SCLK") (class "Default")
      (node (ref "IC3") (pin "15") (pinfunction "PB1(SCK/PCINT1)_15") (pintype "bidirectional"))
    )
    (net (code "49") (name "/SPI_SEL") (class "Default")
      (node (ref "IC3") (pin "14") (pinfunction "PB0(SS/PCINT0)_14") (pintype "bidirectional"))
    )
    (net (code "50") (name "/TCK") (class "Default")
      (node (ref "IC1") (pin "6") (pinfunction "TCK_6") (pintype "bidirectional"))
      (node (ref "IC3") (pin "18") (pinfunction "PB4(T1/PCINT4)_18") (pintype "bidirectional"))
      (node (ref "JP3") (pin "3") (pinfunction "3_3") (pintype "passive"))
      (node (ref "R2") (pin "2") (pinfunction "2_2") (pintype "passive"))
    )
    (net (code "51") (name "/TDI_FPGA") (class "Default")
      (node (ref "IC3") (pin "20") (pinfunction "PB6(PCINT6)_20") (pintype "bidirectional"))
      (node (ref "R1") (pin "2") (pinfunction "2_2") (pintype "passive"))
    )
    (net (code "52") (name "/TDO_EXP") (class "Default")
      (node (ref "IC3") (pin "21") (pinfunction "PB7(OC0A/OC1C/PCINT7)_21") (pintype "bidirectional"))
      (node (ref "JP3") (pin "1") (pinfunction "1_1") (pintype "passive"))
    )
    (net (code "53") (name "/TDO_PROM") (class "Default")
      (node (ref "IC1") (pin "17") (pinfunction "TDO_17") (pintype "bidirectional"))
      (node (ref "IC3") (pin "22") (pinfunction "PC7(ICP1/INT4/CLKO)_22") (pintype "bidirectional"))
      (node (ref "JP3") (pin "2") (pinfunction "2_2") (pintype "passive"))
    )
    (net (code "54") (name "/TMS") (class "Default")
      (node (ref "IC1") (pin "5") (pinfunction "TMS_5") (pintype "bidirectional"))
      (node (ref "IC3") (pin "19") (pinfunction "PB5(PCINT5)_19") (pintype "bidirectional"))
      (node (ref "JP3") (pin "5") (pinfunction "5_5") (pintype "passive"))
      (node (ref "R3") (pin "2") (pinfunction "2_2") (pintype "passive"))
    )
    (net (code "55") (name "/TXD") (class "Default")
      (node (ref "IC3") (pin "9") (pinfunction "PD3(INT3/TXD1)_9") (pintype "bidirectional"))
    )
    (net (code "56") (name "/VCC") (class "Default")
      (node (ref "C10") (pin "1") (pinfunction "1_1") (pintype "passive"))
      (node (ref "C11") (pin "1") (pinfunction "1_1") (pintype "passive"))
      (node (ref "C12") (pin "1") (pinfunction "1_1") (pintype "passive"))
      (node (ref "C13") (pin "1") (pinfunction "1_1") (pintype "passive"))
      (node (ref "C14") (pin "1") (pinfunction "1_1") (pintype "passive"))
      (node (ref "C15") (pin "1") (pinfunction "1_1") (pintype "passive"))
      (node (ref "C16") (pin "1") (pinfunction "1_1") (pintype "passive"))
      (node (ref "C17") (pin "1") (pinfunction "1_1") (pintype "passive"))
      (node (ref "C26") (pin "1") (pinfunction "1_1") (pintype "passive"))
      (node (ref "C27") (pin "1") (pinfunction "1_1") (pintype "passive"))
      (node (ref "C28") (pin "1") (pinfunction "1_1") (pintype "passive"))
      (node (ref "C29") (pin "1") (pinfunction "1_1") (pintype "passive"))
      (node (ref "C30") (pin "1") (pinfunction "1_1") (pintype "passive"))
      (node (ref "C31") (pin "1") (pinfunction "1_1") (pintype "passive"))
      (node (ref "C32") (pin "1") (pinfunction "1_1") (pintype "passive"))
      (node (ref "C34") (pin "1") (pinfunction "1_1") (pintype "passive"))
      (node (ref "C6") (pin "1") (pinfunction "1_1") (pintype "passive"))
      (node (ref "C7") (pin "1") (pinfunction "1_1") (pintype "passive"))
      (node (ref "C8") (pin "1") (pinfunction "1_1") (pintype "passive"))
      (node (ref "C9") (pin "1") (pinfunction "1_1") (pintype "passive"))
      (node (ref "IC1") (pin "18") (pinfunction "VCCINT_18") (pintype "bidirectional"))
      (node (ref "IC1") (pin "19") (pinfunction "VCCO_19") (pintype "bidirectional"))
      (node (ref "IC1") (pin "20") (pinfunction "VCCJ_20") (pintype "bidirectional"))
      (node (ref "IC2") (pin "8") (pinfunction "VCC_8") (pintype "power_in"))
      (node (ref "IC3") (pin "31") (pinfunction "UVCC_31") (pintype "bidirectional"))
      (node (ref "IC3") (pin "32") (pinfunction "AVCC_32") (pintype "bidirectional"))
      (node (ref "IC3") (pin "4") (pinfunction "VCC_4") (pintype "bidirectional"))
      (node (ref "JP1") (pin "2") (pinfunction "2_2") (pintype "passive"))
      (node (ref "JP3") (pin "4") (pinfunction "4_4") (pintype "passive"))
      (node (ref "Q5") (pin "3") (pinfunction "C_3") (pintype "passive"))
      (node (ref "Q6") (pin "3") (pinfunction "C_3") (pintype "passive"))
      (node (ref "Q7") (pin "3") (pinfunction "C_3") (pintype "passive"))
      (node (ref "Q8") (pin "3") (pinfunction "C_3") (pintype "passive"))
      (node (ref "R22") (pin "1") (pinfunction "1_1") (pintype "passive"))
      (node (ref "R35") (pin "2") (pinfunction "2_2") (pintype "passive"))
      (node (ref "R36") (pin "2") (pinfunction "2_2") (pintype "passive"))
      (node (ref "R37") (pin "2") (pinfunction "2_2") (pintype "passive"))
      (node (ref "R38") (pin "2") (pinfunction "2_2") (pintype "passive"))
      (node (ref "R39") (pin "2") (pinfunction "2_2") (pintype "passive"))
      (node (ref "R4") (pin "2") (pinfunction "2_2") (pintype "passive"))
      (node (ref "R40") (pin "1") (pinfunction "1_1") (pintype "passive"))
      (node (ref "R41") (pin "1") (pinfunction "1_1") (pintype "passive"))
      (node (ref "R42") (pin "1") (pinfunction "1_1") (pintype "passive"))
      (node (ref "R43") (pin "1") (pinfunction "1_1") (pintype "passive"))
      (node (ref "R44") (pin "1") (pinfunction "1_1") (pintype "passive"))
      (node (ref "R45") (pin "1") (pinfunction "1_1") (pintype "passive"))
      (node (ref "R46") (pin "2") (pinfunction "2_2") (pintype "passive"))
      (node (ref "R52") (pin "1") (pinfunction "1_1") (pintype "passive"))
      (node (ref "R6") (pin "2") (pinfunction "2_2") (pintype "passive"))
      (node (ref "SV1") (pin "1") (pinfunction "1_1") (pintype "passive"))
      (node (ref "T1") (pin "3") (pinfunction "G_3") (pintype "passive"))
      (node (ref "T2") (pin "3") (pinfunction "C_3") (pintype "passive"))
      (node (ref "T3") (pin "3") (pinfunction "G_3") (pintype "passive"))
      (node (ref "U$1") (pin "P8") (pinfunction "VCC_P8") (pintype "bidirectional"))
      (node (ref "U$2") (pin "VDD") (pinfunction "VDD_VDD") (pintype "power_in"))
      (node (ref "U$4") (pin "4") (pinfunction "VOUT1_4") (pintype "bidirectional"))
      (node (ref "U$5") (pin "2") (pinfunction "VOUT1_2") (pintype "output"))
      (node (ref "U$5") (pin "3") (pinfunction "VOUT2_3") (pintype "output"))
      (node (ref "U$5") (pin "6") (pinfunction "VOUT3_6") (pintype "output"))
      (node (ref "U$5") (pin "7") (pinfunction "VOUT4_7") (pintype "output"))
      (node (ref "U$6") (pin "P8") (pinfunction "VCC_P8") (pintype "bidirectional"))
      (node (ref "U1") (pin "P106") (pinfunction "VCCO_RIGHT2_P106") (pintype "passive"))
      (node (ref "U1") (pin "P115") (pinfunction "VCCO_TOP0_P115") (pintype "passive"))
      (node (ref "U1") (pin "P126") (pinfunction "VCCO_TOP1_P126") (pintype "passive"))
      (node (ref "U1") (pin "P138") (pinfunction "VCCO_TOP2_P138") (pintype "passive"))
      (node (ref "U1") (pin "P19") (pinfunction "VCCO_LEFT1_P19") (pintype "passive"))
      (node (ref "U1") (pin "P3") (pinfunction "VCCO_LEFT0_P3") (pintype "passive"))
      (node (ref "U1") (pin "P34") (pinfunction "VCCO_LEFT2_P34") (pintype "passive"))
      (node (ref "U1") (pin "P43") (pinfunction "VCCO_BOTTOM0_P43") (pintype "passive"))
      (node (ref "U1") (pin "P54") (pinfunction "VCCO_BOTTOM1_P54") (pintype "passive"))
      (node (ref "U1") (pin "P66") (pinfunction "VCCO_BOTTOM2_P66") (pintype "passive"))
      (node (ref "U1") (pin "P75") (pinfunction "VCCO_RIGHT0_P75") (pintype "passive"))
      (node (ref "U1") (pin "P91") (pinfunction "VCCO_RIGHT1_P91") (pintype "passive"))
    )
    (net (code "57") (name "/VCC5") (class "Default")
      (node (ref "C33") (pin "+") (pinfunction "+_+") (pintype "passive"))
      (node (ref "C35") (pin "+") (pinfunction "+_+") (pintype "passive"))
      (node (ref "C36") (pin "+") (pinfunction "+_+") (pintype "passive"))
      (node (ref "R5") (pin "2") (pinfunction "2_2") (pintype "passive"))
      (node (ref "R7") (pin "2") (pinfunction "2_2") (pintype "passive"))
      (node (ref "REG1.2") (pin "3") (pinfunction "VCC_3") (pintype "bidirectional"))
      (node (ref "REG2.5") (pin "3") (pinfunction "VCC_3") (pintype "bidirectional"))
      (node (ref "U$4") (pin "3") (pinfunction "VCC_3") (pintype "bidirectional"))
      (node (ref "U$5") (pin "4") (pinfunction "VCC_4") (pintype "bidirectional"))
      (node (ref "X3") (pin "5") (pinfunction "5_5") (pintype "passive"))
      (node (ref "X8") (pin "2") (pinfunction "2_2") (pintype "power_in"))
    )
    (net (code "58") (name "/VCCAUX") (class "Default")
      (node (ref "C18") (pin "1") (pinfunction "1_1") (pintype "passive"))
      (node (ref "C19") (pin "1") (pinfunction "1_1") (pintype "passive"))
      (node (ref "C20") (pin "1") (pinfunction "1_1") (pintype "passive"))
      (node (ref "C21") (pin "1") (pinfunction "1_1") (pintype "passive"))
      (node (ref "R50") (pin "2") (pinfunction "2_2") (pintype "passive"))
      (node (ref "REG2.5") (pin "4") (pinfunction "VOUT1_4") (pintype "bidirectional"))
      (node (ref "U1") (pin "P120") (pinfunction "VCCAUX2_P120") (pintype "passive"))
      (node (ref "U1") (pin "P134") (pinfunction "VCCAUX3_P134") (pintype "passive"))
      (node (ref "U1") (pin "P48") (pinfunction "VCCAUX0_P48") (pintype "passive"))
      (node (ref "U1") (pin "P62") (pinfunction "VCCAUX1_P62") (pintype "passive"))
    )
    (net (code "59") (name "/VCCINT") (class "Default")
      (node (ref "C22") (pin "1") (pinfunction "1_1") (pintype "passive"))
      (node (ref "C23") (pin "1") (pinfunction "1_1") (pintype "passive"))
      (node (ref "C24") (pin "1") (pinfunction "1_1") (pintype "passive"))
      (node (ref "C25") (pin "1") (pinfunction "1_1") (pintype "passive"))
      (node (ref "REG1.2") (pin "4") (pinfunction "VOUT1_4") (pintype "bidirectional"))
      (node (ref "U1") (pin "P121") (pinfunction "VCCINT2_P121") (pintype "passive"))
      (node (ref "U1") (pin "P133") (pinfunction "VCCINT3_P133") (pintype "passive"))
      (node (ref "U1") (pin "P49") (pinfunction "VCCINT0_P49") (pintype "passive"))
      (node (ref "U1") (pin "P61") (pinfunction "VCCINT1_P61") (pintype "passive"))
    )
    (net (code "60") (name "/VCC_B3") (class "Default")
      (node (ref "R11") (pin "2") (pinfunction "2_2") (pintype "passive"))
    )
    (net (code "61") (name "/X") (class "Default")
      (node (ref "U1") (pin "P70") (pinfunction "IOVREF_4_P70") (pintype "bidirectional"))
    )
    (net (code "65") (name "/XXCSYNC") (class "Default")
      (node (ref "U1") (pin "P137") (pinfunction "IO_L27N_0_P137") (pintype "bidirectional"))
    )
    (net (code "67") (name "GND") (class "Default")
      (node (ref "C1") (pin "1") (pinfunction "1_1") (pintype "passive"))
      (node (ref "C10") (pin "2") (pinfunction "2_2") (pintype "passive"))
      (node (ref "C11") (pin "2") (pinfunction "2_2") (pintype "passive"))
      (node (ref "C12") (pin "2") (pinfunction "2_2") (pintype "passive"))
      (node (ref "C13") (pin "2") (pinfunction "2_2") (pintype "passive"))
      (node (ref "C14") (pin "2") (pinfunction "2_2") (pintype "passive"))
      (node (ref "C15") (pin "2") (pinfunction "2_2") (pintype "passive"))
      (node (ref "C16") (pin "2") (pinfunction "2_2") (pintype "passive"))
      (node (ref "C17") (pin "2") (pinfunction "2_2") (pintype "passive"))
      (node (ref "C18") (pin "2") (pinfunction "2_2") (pintype "passive"))
      (node (ref "C19") (pin "2") (pinfunction "2_2") (pintype "passive"))
      (node (ref "C20") (pin "2") (pinfunction "2_2") (pintype "passive"))
      (node (ref "C21") (pin "2") (pinfunction "2_2") (pintype "passive"))
      (node (ref "C22") (pin "2") (pinfunction "2_2") (pintype "passive"))
      (node (ref "C23") (pin "2") (pinfunction "2_2") (pintype "passive"))
      (node (ref "C24") (pin "2") (pinfunction "2_2") (pintype "passive"))
      (node (ref "C25") (pin "2") (pinfunction "2_2") (pintype "passive"))
      (node (ref "C26") (pin "2") (pinfunction "2_2") (pintype "passive"))
      (node (ref "C27") (pin "2") (pinfunction "2_2") (pintype "passive"))
      (node (ref "C28") (pin "2") (pinfunction "2_2") (pintype "passive"))
      (node (ref "C29") (pin "2") (pinfunction "2_2") (pintype "passive"))
      (node (ref "C30") (pin "2") (pinfunction "2_2") (pintype "passive"))
      (node (ref "C31") (pin "2") (pinfunction "2_2") (pintype "passive"))
      (node (ref "C32") (pin "2") (pinfunction "2_2") (pintype "passive"))
      (node (ref "C33") (pin "-") (pinfunction "-_-") (pintype "passive"))
      (node (ref "C34") (pin "2") (pinfunction "2_2") (pintype "passive"))
      (node (ref "C35") (pin "-") (pinfunction "-_-") (pintype "passive"))
      (node (ref "C36") (pin "-") (pinfunction "-_-") (pintype "passive"))
      (node (ref "C5") (pin "1") (pinfunction "1_1") (pintype "passive"))
      (node (ref "C6") (pin "2") (pinfunction "2_2") (pintype "passive"))
      (node (ref "C7") (pin "2") (pinfunction "2_2") (pintype "passive"))
      (node (ref "C8") (pin "2") (pinfunction "2_2") (pintype "passive"))
      (node (ref "C9") (pin "2") (pinfunction "2_2") (pintype "passive"))
      (node (ref "IC1") (pin "11") (pinfunction "GND_11") (pintype "bidirectional"))
      (node (ref "IC2") (pin "4") (pinfunction "GND_4") (pintype "power_in"))
      (node (ref "IC3") (pin "3") (pinfunction "GND_3") (pintype "bidirectional"))
      (node (ref "JP1") (pin "1") (pinfunction "1_1") (pintype "passive"))
      (node (ref "JP3") (pin "6") (pinfunction "6_6") (pintype "passive"))
      (node (ref "R12") (pin "1") (pinfunction "1_1") (pintype "passive"))
      (node (ref "R17") (pin "1") (pinfunction "1_1") (pintype "passive"))
      (node (ref "R19") (pin "1") (pinfunction "1_1") (pintype "passive"))
      (node (ref "R21") (pin "1") (pinfunction "1_1") (pintype "passive"))
      (node (ref "REG1.2") (pin "1") (pinfunction "GND_1") (pintype "bidirectional"))
      (node (ref "REG2.5") (pin "1") (pinfunction "GND_1") (pintype "bidirectional"))
      (node (ref "RESET_SW") (pin "2") (pinfunction "2_2") (pintype "passive"))
      (node (ref "SV1") (pin "2") (pinfunction "2_2") (pintype "passive"))
      (node (ref "U$1") (pin "P24") (pinfunction "VSS_P24") (pintype "bidirectional"))
      (node (ref "U$1") (pin "P30") (pinfunction "CE_P30") (pintype "bidirectional"))
      (node (ref "U$2") (pin "GND") (pinfunction "GND_GND") (pintype "power_in"))
      (node (ref "U$4") (pin "1") (pinfunction "GND_1") (pintype "bidirectional"))
      (node (ref "U$5") (pin "1") (pinfunction "GND_1") (pintype "bidirectional"))
      (node (ref "U$6") (pin "P24") (pinfunction "VSS_P24") (pintype "bidirectional"))
      (node (ref "U$6") (pin "P30") (pinfunction "CE_P30") (pintype "bidirectional"))
      (node (ref "U1") (pin "P101") (pinfunction "GND11_P101") (pintype "passive"))
      (node (ref "U1") (pin "P114") (pinfunction "GND12_P114") (pintype "passive"))
      (node (ref "U1") (pin "P117") (pinfunction "GND13_P117") (pintype "passive"))
      (node (ref "U1") (pin "P136") (pinfunction "GND14_P136") (pintype "passive"))
      (node (ref "U1") (pin "P139") (pinfunction "GND15_P139") (pintype "passive"))
      (node (ref "U1") (pin "P16") (pinfunction "GND1_P16") (pintype "passive"))
      (node (ref "U1") (pin "P22") (pinfunction "GND2_P22") (pintype "passive"))
      (node (ref "U1") (pin "P29") (pinfunction "GND3_P29") (pintype "passive"))
      (node (ref "U1") (pin "P37") (pinfunction "M1_P37") (pintype "bidirectional"))
      (node (ref "U1") (pin "P38") (pinfunction "M0_P38") (pintype "bidirectional"))
      (node (ref "U1") (pin "P39") (pinfunction "M2_P39") (pintype "bidirectional"))
      (node (ref "U1") (pin "P42") (pinfunction "GND4_P42") (pintype "passive"))
      (node (ref "U1") (pin "P45") (pinfunction "GND5_P45") (pintype "passive"))
      (node (ref "U1") (pin "P64") (pinfunction "GND6_P64") (pintype "passive"))
      (node (ref "U1") (pin "P67") (pinfunction "GND7_P67") (pintype "passive"))
      (node (ref "U1") (pin "P81") (pinfunction "GND8_P81") (pintype "passive"))
      (node (ref "U1") (pin "P88") (pinfunction "GND9_P88") (pintype "passive"))
      (node (ref "U1") (pin "P9") (pinfunction "GND0_P9") (pintype "passive"))
      (node (ref "U1") (pin "P94") (pinfunction "GND10_P94") (pintype "passive"))
      (node (ref "X1") (pin "3") (pinfunction "2_3") (pintype "passive"))
      (node (ref "X2") (pin "13") (pinfunction "13_13") (pintype "passive"))
      (node (ref "X2") (pin "14") (pinfunction "14_14") (pintype "passive"))
      (node (ref "X2") (pin "17") (pinfunction "17_17") (pintype "passive"))
      (node (ref "X2") (pin "18") (pinfunction "18_18") (pintype "passive"))
      (node (ref "X2") (pin "21") (pinfunction "21_21") (pintype "passive"))
      (node (ref "X2") (pin "4") (pinfunction "4_4") (pintype "passive"))
      (node (ref "X2") (pin "5") (pinfunction "5_5") (pintype "passive"))
      (node (ref "X2") (pin "9") (pinfunction "9_9") (pintype "passive"))
      (node (ref "X3") (pin "3") (pinfunction "3_3") (pintype "passive"))
      (node (ref "X3") (pin "SH1") (pinfunction "PE1_SH1") (pintype "power_in"))
      (node (ref "X3") (pin "SH2") (pinfunction "PE2_SH2") (pintype "power_in"))
      (node (ref "X3") (pin "SH3") (pinfunction "PE3_SH3") (pintype "power_in"))
      (node (ref "X4") (pin "8") (pinfunction "F_8") (pintype "passive"))
      (node (ref "X4") (pin "G1") (pinfunction "G1_G1") (pintype "passive"))
      (node (ref "X5") (pin "8") (pinfunction "F_8") (pintype "passive"))
      (node (ref "X5") (pin "G1") (pinfunction "G1_G1") (pintype "passive"))
      (node (ref "X8") (pin "1") (pinfunction "1_1") (pintype "power_in"))
      (node (ref "X8") (pin "3") (pinfunction "3_3") (pintype "power_in"))
    )
    (net (code "68") (name "Net-(C1-Pad2)") (class "Default")
      (node (ref "C1") (pin "2") (pinfunction "2_2") (pintype "passive"))
      (node (ref "R23") (pin "2") (pinfunction "2_2") (pintype "passive"))
      (node (ref "R48") (pin "1") (pinfunction "1_1") (pintype "passive"))
    )
    (net (code "69") (name "Net-(C2-Pad1)") (class "Default")
      (node (ref "C2") (pin "1") (pinfunction "1_1") (pintype "passive"))
      (node (ref "R17") (pin "2") (pinfunction "2_2") (pintype "passive"))
      (node (ref "X1") (pin "1") (pinfunction "1_1") (pintype "passive"))
    )
    (net (code "70") (name "Net-(C3-Pad1)") (class "Default")
      (node (ref "C3") (pin "1") (pinfunction "1_1") (pintype "passive"))
      (node (ref "R48") (pin "2") (pinfunction "2_2") (pintype "passive"))
    )
    (net (code "71") (name "Net-(C4-Pad1)") (class "Default")
      (node (ref "C4") (pin "1") (pinfunction "1_1") (pintype "passive"))
      (node (ref "R49") (pin "2") (pinfunction "2_2") (pintype "passive"))
    )
    (net (code "72") (name "Net-(C5-Pad2)") (class "Default")
      (node (ref "C5") (pin "2") (pinfunction "2_2") (pintype "passive"))
      (node (ref "R34") (pin "2") (pinfunction "2_2") (pintype "passive"))
      (node (ref "R49") (pin "1") (pinfunction "1_1") (pintype "passive"))
    )
    (net (code "73") (name "Net-(IC1-CLK)") (class "Default")
      (node (ref "IC1") (pin "3") (pinfunction "CLK_3") (pintype "bidirectional"))
      (node (ref "U1") (pin "P72") (pinfunction "CCLK_P72") (pintype "bidirectional"))
    )
    (net (code "74") (name "Net-(IC1-TDI)") (class "Default")
      (node (ref "IC1") (pin "4") (pinfunction "TDI_4") (pintype "bidirectional"))
      (node (ref "U1") (pin "P109") (pinfunction "TDO_P109") (pintype "bidirectional"))
    )
    (net (code "75") (name "Net-(IC1-{slash}CE)") (class "Default")
      (node (ref "IC1") (pin "10") (pinfunction "/CE_10") (pintype "bidirectional"))
      (node (ref "U1") (pin "P71") (pinfunction "DONE_P71") (pintype "bidirectional"))
    )
    (net (code "76") (name "Net-(IC1-{slash}CF)") (class "Default")
      (node (ref "IC1") (pin "7") (pinfunction "/CF_7") (pintype "bidirectional"))
      (node (ref "U1") (pin "P143") (pinfunction "PROG_B_P143") (pintype "bidirectional"))
    )
    (net (code "77") (name "Net-(IC3-D+)") (class "Default")
      (node (ref "IC3") (pin "29") (pinfunction "D+_29") (pintype "bidirectional"))
      (node (ref "R54") (pin "2") (pinfunction "2_2") (pintype "passive"))
    )
    (net (code "78") (name "Net-(IC3-D-)") (class "Default")
      (node (ref "IC3") (pin "30") (pinfunction "D-_30") (pintype "bidirectional"))
      (node (ref "R53") (pin "2") (pinfunction "2_2") (pintype "passive"))
    )
    (net (code "79") (name "Net-(IC3-UGND)") (class "Default")
      (node (ref "IC3") (pin "28") (pinfunction "UGND_28") (pintype "bidirectional"))
      (node (ref "X6") (pin "4") (pinfunction "4_4") (pintype "passive"))
    )
    (net (code "80") (name "Net-(Q5-B)") (class "Default")
      (node (ref "Q5") (pin "1") (pinfunction "B_1") (pintype "passive"))
      (node (ref "R8") (pin "2") (pinfunction "2_2") (pintype "passive"))
    )
    (net (code "81") (name "Net-(Q5-E)") (class "Default")
      (node (ref "Q5") (pin "2") (pinfunction "E_2") (pintype "passive"))
      (node (ref "R13") (pin "2") (pinfunction "2_2") (pintype "passive"))
      (node (ref "R14") (pin "2") (pinfunction "2_2") (pintype "passive"))
    )
    (net (code "82") (name "Net-(Q6-B)") (class "Default")
      (node (ref "Q6") (pin "1") (pinfunction "B_1") (pintype "passive"))
      (node (ref "R10") (pin "2") (pinfunction "2_2") (pintype "passive"))
      (node (ref "R9") (pin "2") (pinfunction "2_2") (pintype "passive"))
    )
    (net (code "83") (name "Net-(Q6-E)") (class "Default")
      (node (ref "Q6") (pin "2") (pinfunction "E_2") (pintype "passive"))
      (node (ref "R15") (pin "2") (pinfunction "2_2") (pintype "passive"))
      (node (ref "R16") (pin "2") (pinfunction "2_2") (pintype "passive"))
      (node (ref "R20") (pin "2") (pinfunction "2_2") (pintype "passive"))
    )
    (net (code "84") (name "Net-(Q7-B)") (class "Default")
      (node (ref "Q7") (pin "1") (pinfunction "B_1") (pintype "passive"))
      (node (ref "R29") (pin "2") (pinfunction "2_2") (pintype "passive"))
      (node (ref "R30") (pin "2") (pinfunction "2_2") (pintype "passive"))
    )
    (net (code "85") (name "Net-(Q7-E)") (class "Default")
      (node (ref "Q7") (pin "2") (pinfunction "E_2") (pintype "passive"))
      (node (ref "R31") (pin "2") (pinfunction "2_2") (pintype "passive"))
      (node (ref "R32") (pin "2") (pinfunction "2_2") (pintype "passive"))
      (node (ref "R33") (pin "2") (pinfunction "2_2") (pintype "passive"))
    )
    (net (code "86") (name "Net-(Q8-B)") (class "Default")
      (node (ref "Q8") (pin "1") (pinfunction "B_1") (pintype "passive"))
      (node (ref "R24") (pin "2") (pinfunction "2_2") (pintype "passive"))
      (node (ref "R25") (pin "2") (pinfunction "2_2") (pintype "passive"))
    )
    (net (code "87") (name "Net-(Q8-E)") (class "Default")
      (node (ref "Q8") (pin "2") (pinfunction "E_2") (pintype "passive"))
      (node (ref "R26") (pin "2") (pinfunction "2_2") (pintype "passive"))
      (node (ref "R27") (pin "2") (pinfunction "2_2") (pintype "passive"))
      (node (ref "R28") (pin "2") (pinfunction "2_2") (pintype "passive"))
    )
    (net (code "88") (name "Net-(R18-Pad2)") (class "Default")
      (node (ref "R18") (pin "2") (pinfunction "2_2") (pintype "passive"))
      (node (ref "R22") (pin "2") (pinfunction "2_2") (pintype "passive"))
    )
    (net (code "89") (name "Net-(R53-Pad1)") (class "Default")
      (node (ref "R53") (pin "1") (pinfunction "1_1") (pintype "passive"))
      (node (ref "X6") (pin "2") (pinfunction "2_2") (pintype "passive"))
    )
    (net (code "90") (name "Net-(R54-Pad1)") (class "Default")
      (node (ref "R54") (pin "1") (pinfunction "1_1") (pintype "passive"))
      (node (ref "X6") (pin "3") (pinfunction "3_3") (pintype "passive"))
    )
    (net (code "91") (name "Net-(T2-B)") (class "Default")
      (node (ref "C2") (pin "2") (pinfunction "2_2") (pintype "passive"))
      (node (ref "R18") (pin "1") (pinfunction "1_1") (pintype "passive"))
      (node (ref "R19") (pin "2") (pinfunction "2_2") (pintype "passive"))
      (node (ref "T2") (pin "1") (pinfunction "B_1") (pintype "passive"))
    )
    (net (code "92") (name "Net-(U$1-A0)") (class "Default")
      (node (ref "U$1") (pin "P20") (pinfunction "A0_P20") (pintype "bidirectional"))
      (node (ref "U1") (pin "P77") (pinfunction "IO_L20P_3_P77") (pintype "bidirectional"))
    )
    (net (code "93") (name "Net-(U$1-A1)") (class "Default")
      (node (ref "U$1") (pin "P19") (pinfunction "A1_P19") (pintype "bidirectional"))
      (node (ref "U1") (pin "P76") (pinfunction "IO_P76") (pintype "bidirectional"))
    )
    (net (code "94") (name "Net-(U$1-A2)") (class "Default")
      (node (ref "U$1") (pin "P18") (pinfunction "A2_P18") (pintype "bidirectional"))
      (node (ref "U1") (pin "P74") (pinfunction "IO_L01N_3VRP_3_P74") (pintype "bidirectional"))
    )
    (net (code "95") (name "Net-(U$1-A3)") (class "Default")
      (node (ref "U$1") (pin "P17") (pinfunction "A3_P17") (pintype "bidirectional"))
      (node (ref "U1") (pin "P73") (pinfunction "IO_L01P_3VRN_3_P73") (pintype "bidirectional"))
    )
    (net (code "96") (name "Net-(U$1-A4)") (class "Default")
      (node (ref "U$1") (pin "P16") (pinfunction "A4_P16") (pintype "bidirectional"))
      (node (ref "U1") (pin "P108") (pinfunction "IO_L01N_2VRP_2_P108") (pintype "bidirectional"))
    )
    (net (code "97") (name "Net-(U$1-A5)") (class "Default")
      (node (ref "U$1") (pin "P15") (pinfunction "A5_P15") (pintype "bidirectional"))
      (node (ref "U1") (pin "P107") (pinfunction "IO_L01P_2VRN_2_P107") (pintype "bidirectional"))
    )
    (net (code "98") (name "Net-(U$1-A6)") (class "Default")
      (node (ref "U$1") (pin "P14") (pinfunction "A6_P14") (pintype "bidirectional"))
      (node (ref "U1") (pin "P105") (pinfunction "IO_L20N_2_P105") (pintype "bidirectional"))
    )
    (net (code "99") (name "Net-(U$1-A7)") (class "Default")
      (node (ref "U$1") (pin "P13") (pinfunction "A7_P13") (pintype "bidirectional"))
      (node (ref "U1") (pin "P104") (pinfunction "IO_L20P_2_P104") (pintype "bidirectional"))
    )
    (net (code "100") (name "Net-(U$1-A8)") (class "Default")
      (node (ref "U$1") (pin "P3") (pinfunction "A8_P3") (pintype "bidirectional"))
      (node (ref "U1") (pin "P93") (pinfunction "IO_L40N_2_P93") (pintype "bidirectional"))
    )
    (net (code "101") (name "Net-(U$1-A9)") (class "Default")
      (node (ref "U$1") (pin "P2") (pinfunction "A9_P2") (pintype "bidirectional"))
      (node (ref "U1") (pin "P92") (pinfunction "IO_L40P_2VREF_2_P92") (pintype "bidirectional"))
    )
    (net (code "102") (name "Net-(U$1-A10)") (class "Default")
      (node (ref "U$1") (pin "P31") (pinfunction "A10_P31") (pintype "bidirectional"))
      (node (ref "U1") (pin "P87") (pinfunction "IO_L24N_3_P87") (pintype "bidirectional"))
    )
    (net (code "103") (name "Net-(U$1-A11)") (class "Default")
      (node (ref "U$1") (pin "P1") (pinfunction "A11_P1") (pintype "bidirectional"))
      (node (ref "U1") (pin "P90") (pinfunction "IO_L40N_3VREF_3_P90") (pintype "bidirectional"))
    )
    (net (code "104") (name "Net-(U$1-A12)") (class "Default")
      (node (ref "U$1") (pin "P12") (pinfunction "A12_P12") (pintype "bidirectional"))
      (node (ref "U1") (pin "P103") (pinfunction "IO_L21N_2_P103") (pintype "bidirectional"))
    )
    (net (code "105") (name "Net-(U$1-A13)") (class "Default")
      (node (ref "U$1") (pin "P4") (pinfunction "A13_P4") (pintype "bidirectional"))
      (node (ref "U1") (pin "P95") (pinfunction "IO_L24P_2_P95") (pintype "bidirectional"))
    )
    (net (code "106") (name "Net-(U$1-A14)") (class "Default")
      (node (ref "U$1") (pin "P11") (pinfunction "A14_P11") (pintype "bidirectional"))
      (node (ref "U1") (pin "P102") (pinfunction "IO_L21P_2_P102") (pintype "bidirectional"))
    )
    (net (code "107") (name "Net-(U$1-A15)") (class "Default")
      (node (ref "U$1") (pin "P7") (pinfunction "A15_P7") (pintype "bidirectional"))
      (node (ref "U1") (pin "P98") (pinfunction "IO_L23N_2VREF_2_P98") (pintype "bidirectional"))
    )
    (net (code "108") (name "Net-(U$1-A16)") (class "Default")
      (node (ref "U$1") (pin "P10") (pinfunction "A16_P10") (pintype "bidirectional"))
      (node (ref "U1") (pin "P100") (pinfunction "IO_L22N_2_P100") (pintype "bidirectional"))
    )
    (net (code "109") (name "Net-(U$1-A17)") (class "Default")
      (node (ref "U$1") (pin "P6") (pinfunction "A17_P6") (pintype "bidirectional"))
      (node (ref "U1") (pin "P97") (pinfunction "IO_L23P_2_P97") (pintype "bidirectional"))
    )
    (net (code "110") (name "Net-(U$1-A18)") (class "Default")
      (node (ref "U$1") (pin "P9") (pinfunction "A18_P9") (pintype "bidirectional"))
      (node (ref "U1") (pin "P99") (pinfunction "IO_L22P_2_P99") (pintype "bidirectional"))
    )
    (net (code "111") (name "Net-(U$1-DQ0)") (class "Default")
      (node (ref "U$1") (pin "P21") (pinfunction "DQ0_P21") (pintype "bidirectional"))
      (node (ref "U1") (pin "P78") (pinfunction "IO_L20N_3_P78") (pintype "bidirectional"))
    )
    (net (code "112") (name "Net-(U$1-DQ1)") (class "Default")
      (node (ref "U$1") (pin "P22") (pinfunction "DQ1_P22") (pintype "bidirectional"))
      (node (ref "U1") (pin "P79") (pinfunction "IO_L21P_3_P79") (pintype "bidirectional"))
    )
    (net (code "113") (name "Net-(U$1-DQ2)") (class "Default")
      (node (ref "U$1") (pin "P23") (pinfunction "DQ2_P23") (pintype "bidirectional"))
      (node (ref "U1") (pin "P80") (pinfunction "IO_L21N_3_P80") (pintype "bidirectional"))
    )
    (net (code "114") (name "Net-(U$1-DQ3)") (class "Default")
      (node (ref "U$1") (pin "P25") (pinfunction "DQ3_P25") (pintype "bidirectional"))
      (node (ref "U1") (pin "P82") (pinfunction "IO_L22P_3_P82") (pintype "bidirectional"))
    )
    (net (code "115") (name "Net-(U$1-DQ4)") (class "Default")
      (node (ref "U$1") (pin "P26") (pinfunction "DQ4_P26") (pintype "bidirectional"))
      (node (ref "U1") (pin "P83") (pinfunction "IO_L22N_3_P83") (pintype "bidirectional"))
    )
    (net (code "116") (name "Net-(U$1-DQ5)") (class "Default")
      (node (ref "U$1") (pin "P27") (pinfunction "DQ5_P27") (pintype "bidirectional"))
      (node (ref "U1") (pin "P84") (pinfunction "IO_L23P_3VREF_3_P84") (pintype "bidirectional"))
    )
    (net (code "117") (name "Net-(U$1-DQ6)") (class "Default")
      (node (ref "U$1") (pin "P28") (pinfunction "DQ6_P28") (pintype "bidirectional"))
      (node (ref "U1") (pin "P85") (pinfunction "IO_L23N_3_P85") (pintype "bidirectional"))
    )
    (net (code "118") (name "Net-(U$1-DQ7)") (class "Default")
      (node (ref "U$1") (pin "P29") (pinfunction "DQ7_P29") (pintype "bidirectional"))
      (node (ref "U1") (pin "P86") (pinfunction "IO_L24P_3_P86") (pintype "bidirectional"))
    )
    (net (code "119") (name "Net-(U$1-OE)") (class "Default")
      (node (ref "U$1") (pin "P32") (pinfunction "OE_P32") (pintype "bidirectional"))
      (node (ref "U1") (pin "P89") (pinfunction "IO_L40P_3_P89") (pintype "bidirectional"))
    )
    (net (code "120") (name "Net-(U$1-WE)") (class "Default")
      (node (ref "U$1") (pin "P5") (pinfunction "WE_P5") (pintype "bidirectional"))
      (node (ref "U1") (pin "P96") (pinfunction "IO_L24N_2_P96") (pintype "bidirectional"))
    )
    (net (code "121") (name "Net-(U$6-A0)") (class "Default")
      (node (ref "U$6") (pin "P20") (pinfunction "A0_P20") (pintype "bidirectional"))
      (node (ref "U1") (pin "P24") (pinfunction "IO_L24N_6VREF_6_P24") (pintype "bidirectional"))
    )
    (net (code "122") (name "Net-(U$6-A1)") (class "Default")
      (node (ref "U$6") (pin "P19") (pinfunction "A1_P19") (pintype "bidirectional"))
      (node (ref "U1") (pin "P23") (pinfunction "IO_L24P_6_P23") (pintype "bidirectional"))
    )
    (net (code "123") (name "Net-(U$6-A2)") (class "Default")
      (node (ref "U$6") (pin "P18") (pinfunction "A2_P18") (pintype "bidirectional"))
      (node (ref "U1") (pin "P21") (pinfunction "IO_L40N_6_P21") (pintype "bidirectional"))
    )
    (net (code "124") (name "Net-(U$6-A3)") (class "Default")
      (node (ref "U$6") (pin "P17") (pinfunction "A3_P17") (pintype "bidirectional"))
      (node (ref "U1") (pin "P20") (pinfunction "IO_L40P_6VREF_6_P20") (pintype "bidirectional"))
    )
    (net (code "125") (name "Net-(U$6-A4)") (class "Default")
      (node (ref "U$6") (pin "P16") (pinfunction "A4_P16") (pintype "bidirectional"))
      (node (ref "U1") (pin "P18") (pinfunction "IO_L40N_7VREF_7_P18") (pintype "bidirectional"))
    )
    (net (code "126") (name "Net-(U$6-A5)") (class "Default")
      (node (ref "U$6") (pin "P15") (pinfunction "A5_P15") (pintype "bidirectional"))
      (node (ref "U1") (pin "P17") (pinfunction "IO_L40P_7_P17") (pintype "bidirectional"))
    )
    (net (code "127") (name "Net-(U$6-A6)") (class "Default")
      (node (ref "U$6") (pin "P14") (pinfunction "A6_P14") (pintype "bidirectional"))
      (node (ref "U1") (pin "P15") (pinfunction "IO_L24N_7_P15") (pintype "bidirectional"))
    )
    (net (code "128") (name "Net-(U$6-A7)") (class "Default")
      (node (ref "U$6") (pin "P13") (pinfunction "A7_P13") (pintype "bidirectional"))
      (node (ref "U1") (pin "P14") (pinfunction "IO_L24P_7_P14") (pintype "bidirectional"))
    )
    (net (code "129") (name "Net-(U$6-A8)") (class "Default")
      (node (ref "U$6") (pin "P3") (pinfunction "A8_P3") (pintype "bidirectional"))
      (node (ref "U1") (pin "P4") (pinfunction "IOVREF_7_P4") (pintype "bidirectional"))
    )
    (net (code "130") (name "Net-(U$6-A9)") (class "Default")
      (node (ref "U$6") (pin "P2") (pinfunction "A9_P2") (pintype "bidirectional"))
      (node (ref "U1") (pin "P2") (pinfunction "IO_L01N_7VRP_7_P2") (pintype "bidirectional"))
    )
    (net (code "131") (name "Net-(U$6-A10)") (class "Default")
      (node (ref "U$6") (pin "P31") (pinfunction "A10_P31") (pintype "bidirectional"))
      (node (ref "U1") (pin "P35") (pinfunction "IO_L01P_6VRN_6_P35") (pintype "bidirectional"))
    )
    (net (code "132") (name "Net-(U$6-A11)") (class "Default")
      (node (ref "U$6") (pin "P1") (pinfunction "A11_P1") (pintype "bidirectional"))
      (node (ref "U1") (pin "P1") (pinfunction "IO_L01P_7VRN_7_P1") (pintype "bidirectional"))
    )
    (net (code "133") (name "Net-(U$6-A12)") (class "Default")
      (node (ref "U$6") (pin "P12") (pinfunction "A12_P12") (pintype "bidirectional"))
      (node (ref "U1") (pin "P13") (pinfunction "IO_L23N_7_P13") (pintype "bidirectional"))
    )
    (net (code "134") (name "Net-(U$6-A13)") (class "Default")
      (node (ref "U$6") (pin "P4") (pinfunction "A13_P4") (pintype "bidirectional"))
      (node (ref "U1") (pin "P5") (pinfunction "IO_L20P_7_P5") (pintype "bidirectional"))
    )
    (net (code "135") (name "Net-(U$6-A14)") (class "Default")
      (node (ref "U$6") (pin "P11") (pinfunction "A14_P11") (pintype "bidirectional"))
      (node (ref "U1") (pin "P12") (pinfunction "IO_L23P_7_P12") (pintype "bidirectional"))
    )
    (net (code "136") (name "Net-(U$6-A15)") (class "Default")
      (node (ref "U$6") (pin "P7") (pinfunction "A15_P7") (pintype "bidirectional"))
      (node (ref "U1") (pin "P8") (pinfunction "IO_L21N_7_P8") (pintype "bidirectional"))
    )
    (net (code "137") (name "Net-(U$6-A16)") (class "Default")
      (node (ref "U$6") (pin "P10") (pinfunction "A16_P10") (pintype "bidirectional"))
      (node (ref "U1") (pin "P11") (pinfunction "IO_L22N_7_P11") (pintype "bidirectional"))
    )
    (net (code "138") (name "Net-(U$6-A17)") (class "Default")
      (node (ref "U$6") (pin "P6") (pinfunction "A17_P6") (pintype "bidirectional"))
      (node (ref "U1") (pin "P7") (pinfunction "IO_L21P_7_P7") (pintype "bidirectional"))
    )
    (net (code "139") (name "Net-(U$6-A18)") (class "Default")
      (node (ref "U$6") (pin "P9") (pinfunction "A18_P9") (pintype "bidirectional"))
      (node (ref "U1") (pin "P10") (pinfunction "IO_L22P_7_P10") (pintype "bidirectional"))
    )
    (net (code "140") (name "Net-(U$6-DQ0)") (class "Default")
      (node (ref "U$6") (pin "P21") (pinfunction "DQ0_P21") (pintype "bidirectional"))
      (node (ref "U1") (pin "P25") (pinfunction "IO_L23P_6_P25") (pintype "bidirectional"))
    )
    (net (code "141") (name "Net-(U$6-DQ1)") (class "Default")
      (node (ref "U$6") (pin "P22") (pinfunction "DQ1_P22") (pintype "bidirectional"))
      (node (ref "U1") (pin "P26") (pinfunction "IO_L23N_6_P26") (pintype "bidirectional"))
    )
    (net (code "142") (name "Net-(U$6-DQ2)") (class "Default")
      (node (ref "U$6") (pin "P23") (pinfunction "DQ2_P23") (pintype "bidirectional"))
      (node (ref "U1") (pin "P27") (pinfunction "IO_L22P_6_P27") (pintype "bidirectional"))
    )
    (net (code "143") (name "Net-(U$6-DQ3)") (class "Default")
      (node (ref "U$6") (pin "P25") (pinfunction "DQ3_P25") (pintype "bidirectional"))
      (node (ref "U1") (pin "P28") (pinfunction "IO_L22N_6_P28") (pintype "bidirectional"))
    )
    (net (code "144") (name "Net-(U$6-DQ4)") (class "Default")
      (node (ref "U$6") (pin "P26") (pinfunction "DQ4_P26") (pintype "bidirectional"))
      (node (ref "U1") (pin "P30") (pinfunction "IO_L21P_6_P30") (pintype "bidirectional"))
    )
    (net (code "145") (name "Net-(U$6-DQ5)") (class "Default")
      (node (ref "U$6") (pin "P27") (pinfunction "DQ5_P27") (pintype "bidirectional"))
      (node (ref "U1") (pin "P31") (pinfunction "IO_L21N_6_P31") (pintype "bidirectional"))
    )
    (net (code "146") (name "Net-(U$6-DQ6)") (class "Default")
      (node (ref "U$6") (pin "P28") (pinfunction "DQ6_P28") (pintype "bidirectional"))
      (node (ref "U1") (pin "P32") (pinfunction "IO_L20P_6_P32") (pintype "bidirectional"))
    )
    (net (code "147") (name "Net-(U$6-DQ7)") (class "Default")
      (node (ref "U$6") (pin "P29") (pinfunction "DQ7_P29") (pintype "bidirectional"))
      (node (ref "U1") (pin "P33") (pinfunction "IO_L20N_6_P33") (pintype "bidirectional"))
    )
    (net (code "148") (name "Net-(U$6-OE)") (class "Default")
      (node (ref "U$6") (pin "P32") (pinfunction "OE_P32") (pintype "bidirectional"))
      (node (ref "U1") (pin "P36") (pinfunction "IO_L01N_6VRP_6_P36") (pintype "bidirectional"))
    )
    (net (code "149") (name "Net-(U$6-WE)") (class "Default")
      (node (ref "U$6") (pin "P5") (pinfunction "WE_P5") (pintype "bidirectional"))
      (node (ref "U1") (pin "P6") (pinfunction "IO_L20N_7_P6") (pintype "bidirectional"))
    )
    (net (code "150") (name "Net-(U1G-IO_L32N_4GCLK1)") (class "Default")
      (node (ref "SV1") (pin "10") (pinfunction "10_10") (pintype "passive"))
      (node (ref "U1") (pin "P56") (pinfunction "IO_L32N_4GCLK1_P56") (pintype "bidirectional"))
    )
    (net (code "151") (name "Net-(U1N-TCK)") (class "Default")
      (node (ref "R2") (pin "1") (pinfunction "1_1") (pintype "passive"))
      (node (ref "U1") (pin "P110") (pinfunction "TCK_P110") (pintype "bidirectional"))
    )
    (net (code "152") (name "Net-(U1N-TDI)") (class "Default")
      (node (ref "R1") (pin "1") (pinfunction "1_1") (pintype "passive"))
      (node (ref "U1") (pin "P144") (pinfunction "TDI_P144") (pintype "bidirectional"))
    )
    (net (code "153") (name "Net-(U1N-TMS)") (class "Default")
      (node (ref "R3") (pin "1") (pinfunction "1_1") (pintype "passive"))
      (node (ref "U1") (pin "P111") (pinfunction "TMS_P111") (pintype "bidirectional"))
    )
    (net (code "154") (name "Net-(X4A-F)") (class "Default")
      (node (ref "R40") (pin "2") (pinfunction "2_2") (pintype "passive"))
      (node (ref "X4") (pin "1") (pinfunction "F_1") (pintype "passive"))
    )
    (net (code "155") (name "Net-(X4B-F)") (class "Default")
      (node (ref "R41") (pin "2") (pinfunction "2_2") (pintype "passive"))
      (node (ref "X4") (pin "2") (pinfunction "F_2") (pintype "passive"))
    )
    (net (code "156") (name "Net-(X4C-F)") (class "Default")
      (node (ref "R42") (pin "2") (pinfunction "2_2") (pintype "passive"))
      (node (ref "X4") (pin "3") (pinfunction "F_3") (pintype "passive"))
    )
    (net (code "157") (name "Net-(X4D-F)") (class "Default")
      (node (ref "R43") (pin "2") (pinfunction "2_2") (pintype "passive"))
      (node (ref "X4") (pin "4") (pinfunction "F_4") (pintype "passive"))
    )
    (net (code "158") (name "Net-(X4F-F)") (class "Default")
      (node (ref "R44") (pin "2") (pinfunction "2_2") (pintype "passive"))
      (node (ref "X4") (pin "6") (pinfunction "F_6") (pintype "passive"))
    )
    (net (code "159") (name "Net-(X4G-F)") (class "Default")
      (node (ref "R45") (pin "2") (pinfunction "2_2") (pintype "passive"))
      (node (ref "X4") (pin "7") (pinfunction "F_7") (pintype "passive"))
    )
    (net (code "160") (name "Net-(X5A-F)") (class "Default")
      (node (ref "R46") (pin "1") (pinfunction "1_1") (pintype "passive"))
      (node (ref "X5") (pin "1") (pinfunction "F_1") (pintype "passive"))
    )
    (net (code "161") (name "Net-(X5B-F)") (class "Default")
      (node (ref "R39") (pin "1") (pinfunction "1_1") (pintype "passive"))
      (node (ref "X5") (pin "2") (pinfunction "F_2") (pintype "passive"))
    )
    (net (code "162") (name "Net-(X5C-F)") (class "Default")
      (node (ref "R38") (pin "1") (pinfunction "1_1") (pintype "passive"))
      (node (ref "X5") (pin "3") (pinfunction "F_3") (pintype "passive"))
    )
    (net (code "163") (name "Net-(X5D-F)") (class "Default")
      (node (ref "R37") (pin "1") (pinfunction "1_1") (pintype "passive"))
      (node (ref "X5") (pin "4") (pinfunction "F_4") (pintype "passive"))
    )
    (net (code "164") (name "Net-(X5F-F)") (class "Default")
      (node (ref "R36") (pin "1") (pinfunction "1_1") (pintype "passive"))
      (node (ref "X5") (pin "6") (pinfunction "F_6") (pintype "passive"))
    )
    (net (code "165") (name "Net-(X5G-F)") (class "Default")
      (node (ref "R35") (pin "1") (pinfunction "1_1") (pintype "passive"))
      (node (ref "X5") (pin "7") (pinfunction "F_7") (pintype "passive"))
    )
    (net (code "166") (name "unconnected-(IC1-NC.1-Pad2)") (class "Default")
      (node (ref "IC1") (pin "2") (pinfunction "NC.1_2") (pintype "bidirectional"))
    )
    (net (code "167") (name "unconnected-(IC1-NC.2-Pad9)") (class "Default")
      (node (ref "IC1") (pin "9") (pinfunction "NC.2_9") (pintype "bidirectional"))
    )
    (net (code "168") (name "unconnected-(IC1-NC.3-Pad12)") (class "Default")
      (node (ref "IC1") (pin "12") (pinfunction "NC.3_12") (pintype "bidirectional"))
    )
    (net (code "169") (name "unconnected-(IC1-NC.4-Pad14)") (class "Default")
      (node (ref "IC1") (pin "14") (pinfunction "NC.4_14") (pintype "bidirectional"))
    )
    (net (code "170") (name "unconnected-(IC1-NC.5-Pad15)") (class "Default")
      (node (ref "IC1") (pin "15") (pinfunction "NC.5_15") (pintype "bidirectional"))
    )
    (net (code "171") (name "unconnected-(IC1-NC.6-Pad16)") (class "Default")
      (node (ref "IC1") (pin "16") (pinfunction "NC.6_16") (pintype "bidirectional"))
    )
    (net (code "172") (name "unconnected-(IC1-{slash}CEO-Pad13)") (class "Default")
      (node (ref "IC1") (pin "13") (pinfunction "/CEO_13") (pintype "bidirectional"))
    )
    (net (code "173") (name "unconnected-(IC3-PC2(AIN2{slash}PCIN11)-Pad5)") (class "Default")
      (node (ref "IC3") (pin "5") (pinfunction "PC2(AIN2/PCIN11)_5") (pintype "bidirectional"))
    )
    (net (code "174") (name "unconnected-(IC3-PC4(PCINT10)-Pad26)") (class "Default")
      (node (ref "IC3") (pin "26") (pinfunction "PC4(PCINT10)_26") (pintype "bidirectional"))
    )
    (net (code "175") (name "unconnected-(IC3-PC5(OC1B{slash}PCINT9)-Pad25)") (class "Default")
      (node (ref "IC3") (pin "25") (pinfunction "PC5(OC1B/PCINT9)_25") (pintype "bidirectional"))
    )
    (net (code "176") (name "unconnected-(IC3-PC6(OC1A{slash}PCINT8)-Pad23)") (class "Default")
      (node (ref "IC3") (pin "23") (pinfunction "PC6(OC1A/PCINT8)_23") (pintype "bidirectional"))
    )
    (net (code "177") (name "unconnected-(IC3-PD0(INT0{slash}OC0B)-Pad6)") (class "Default")
      (node (ref "IC3") (pin "6") (pinfunction "PD0(INT0/OC0B)_6") (pintype "bidirectional"))
    )
    (net (code "178") (name "unconnected-(IC3-PD1(INT1{slash}AIN0)-Pad7)") (class "Default")
      (node (ref "IC3") (pin "7") (pinfunction "PD1(INT1/AIN0)_7") (pintype "bidirectional"))
    )
    (net (code "179") (name "unconnected-(IC3-PD4(INT5{slash}AIN3)-Pad10)") (class "Default")
      (node (ref "IC3") (pin "10") (pinfunction "PD4(INT5/AIN3)_10") (pintype "bidirectional"))
    )
    (net (code "180") (name "unconnected-(IC3-PD5(XCK{slash}AIN4{slash}PCINT12)-Pad11)") (class "Default")
      (node (ref "IC3") (pin "11") (pinfunction "PD5(XCK/AIN4/PCINT12)_11") (pintype "bidirectional"))
    )
    (net (code "181") (name "unconnected-(IC3-PD6(INT6{slash}AIN5{slash}RTS)-Pad12)") (class "Default")
      (node (ref "IC3") (pin "12") (pinfunction "PD6(INT6/AIN5/RTS)_12") (pintype "bidirectional"))
    )
    (net (code "182") (name "unconnected-(IC3-UCAP-Pad27)") (class "Default")
      (node (ref "IC3") (pin "27") (pinfunction "UCAP_27") (pintype "bidirectional"))
    )
    (net (code "183") (name "unconnected-(IC3-XTAL1-Pad1)") (class "Default")
      (node (ref "IC3") (pin "1") (pinfunction "XTAL1_1") (pintype "bidirectional"))
    )
    (net (code "184") (name "unconnected-(IC3-XTAL2{slash}PC0-Pad2)") (class "Default")
      (node (ref "IC3") (pin "2") (pinfunction "XTAL2/PC0_2") (pintype "bidirectional"))
    )
    (net (code "185") (name "unconnected-(IC3-{slash}RESET(PC1)-Pad24)") (class "Default")
      (node (ref "IC3") (pin "24") (pinfunction "/RESET(PC1)_24") (pintype "bidirectional"))
    )
    (net (code "186") (name "unconnected-(JP1-Pad3)") (class "Default")
      (node (ref "JP1") (pin "3") (pinfunction "3_3") (pintype "passive"))
    )
    (net (code "187") (name "unconnected-(JP1-Pad4)") (class "Default")
      (node (ref "JP1") (pin "4") (pinfunction "4_4") (pintype "passive"))
    )
    (net (code "188") (name "unconnected-(JP1-Pad5)") (class "Default")
      (node (ref "JP1") (pin "5") (pinfunction "5_5") (pintype "passive"))
    )
    (net (code "189") (name "unconnected-(JP1-Pad6)") (class "Default")
      (node (ref "JP1") (pin "6") (pinfunction "6_6") (pintype "passive"))
    )
    (net (code "190") (name "unconnected-(JP1-Pad7)") (class "Default")
      (node (ref "JP1") (pin "7") (pinfunction "7_7") (pintype "passive"))
    )
    (net (code "191") (name "unconnected-(JP1-Pad8)") (class "Default")
      (node (ref "JP1") (pin "8") (pinfunction "8_8") (pintype "passive"))
    )
    (net (code "192") (name "unconnected-(JP1-Pad9)") (class "Default")
      (node (ref "JP1") (pin "9") (pinfunction "9_9") (pintype "passive"))
    )
    (net (code "193") (name "unconnected-(JP1-Pad10)") (class "Default")
      (node (ref "JP1") (pin "10") (pinfunction "10_10") (pintype "passive"))
    )
    (net (code "194") (name "unconnected-(JP1-Pad11)") (class "Default")
      (node (ref "JP1") (pin "11") (pinfunction "11_11") (pintype "passive"))
    )
    (net (code "195") (name "unconnected-(JP1-Pad12)") (class "Default")
      (node (ref "JP1") (pin "12") (pinfunction "12_12") (pintype "passive"))
    )
    (net (code "196") (name "unconnected-(JP1-Pad13)") (class "Default")
      (node (ref "JP1") (pin "13") (pinfunction "13_13") (pintype "passive"))
    )
    (net (code "197") (name "unconnected-(JP1-Pad14)") (class "Default")
      (node (ref "JP1") (pin "14") (pinfunction "14_14") (pintype "passive"))
    )
    (net (code "198") (name "unconnected-(JP1-Pad15)") (class "Default")
      (node (ref "JP1") (pin "15") (pinfunction "15_15") (pintype "passive"))
    )
    (net (code "199") (name "unconnected-(JP1-Pad16)") (class "Default")
      (node (ref "JP1") (pin "16") (pinfunction "16_16") (pintype "passive"))
    )
    (net (code "200") (name "unconnected-(JP1-Pad17)") (class "Default")
      (node (ref "JP1") (pin "17") (pinfunction "17_17") (pintype "passive"))
    )
    (net (code "201") (name "unconnected-(JP1-Pad18)") (class "Default")
      (node (ref "JP1") (pin "18") (pinfunction "18_18") (pintype "passive"))
    )
    (net (code "202") (name "unconnected-(JP1-Pad19)") (class "Default")
      (node (ref "JP1") (pin "19") (pinfunction "19_19") (pintype "passive"))
    )
    (net (code "203") (name "unconnected-(JP1-Pad20)") (class "Default")
      (node (ref "JP1") (pin "20") (pinfunction "20_20") (pintype "passive"))
    )
    (net (code "204") (name "unconnected-(JP2-Pad1)") (class "Default")
      (node (ref "JP2") (pin "1") (pinfunction "1_1") (pintype "passive"))
    )
    (net (code "205") (name "unconnected-(JP2-Pad2)") (class "Default")
      (node (ref "JP2") (pin "2") (pinfunction "2_2") (pintype "passive"))
    )
    (net (code "206") (name "unconnected-(JP2-Pad3)") (class "Default")
      (node (ref "JP2") (pin "3") (pinfunction "3_3") (pintype "passive"))
    )
    (net (code "207") (name "unconnected-(JP2-Pad4)") (class "Default")
      (node (ref "JP2") (pin "4") (pinfunction "4_4") (pintype "passive"))
    )
    (net (code "208") (name "unconnected-(JP2-Pad5)") (class "Default")
      (node (ref "JP2") (pin "5") (pinfunction "5_5") (pintype "passive"))
    )
    (net (code "209") (name "unconnected-(JP2-Pad6)") (class "Default")
      (node (ref "JP2") (pin "6") (pinfunction "6_6") (pintype "passive"))
    )
    (net (code "210") (name "unconnected-(JP2-Pad7)") (class "Default")
      (node (ref "JP2") (pin "7") (pinfunction "7_7") (pintype "passive"))
    )
    (net (code "211") (name "unconnected-(JP2-Pad8)") (class "Default")
      (node (ref "JP2") (pin "8") (pinfunction "8_8") (pintype "passive"))
    )
    (net (code "212") (name "unconnected-(JP2-Pad9)") (class "Default")
      (node (ref "JP2") (pin "9") (pinfunction "9_9") (pintype "passive"))
    )
    (net (code "213") (name "unconnected-(JP2-Pad10)") (class "Default")
      (node (ref "JP2") (pin "10") (pinfunction "10_10") (pintype "passive"))
    )
    (net (code "214") (name "unconnected-(JP2-Pad11)") (class "Default")
      (node (ref "JP2") (pin "11") (pinfunction "11_11") (pintype "passive"))
    )
    (net (code "215") (name "unconnected-(JP2-Pad12)") (class "Default")
      (node (ref "JP2") (pin "12") (pinfunction "12_12") (pintype "passive"))
    )
    (net (code "216") (name "unconnected-(JP2-Pad13)") (class "Default")
      (node (ref "JP2") (pin "13") (pinfunction "13_13") (pintype "passive"))
    )
    (net (code "217") (name "unconnected-(JP2-Pad14)") (class "Default")
      (node (ref "JP2") (pin "14") (pinfunction "14_14") (pintype "passive"))
    )
    (net (code "218") (name "unconnected-(JP2-Pad15)") (class "Default")
      (node (ref "JP2") (pin "15") (pinfunction "15_15") (pintype "passive"))
    )
    (net (code "219") (name "unconnected-(JP2-Pad16)") (class "Default")
      (node (ref "JP2") (pin "16") (pinfunction "16_16") (pintype "passive"))
    )
    (net (code "220") (name "unconnected-(JP2-Pad17)") (class "Default")
      (node (ref "JP2") (pin "17") (pinfunction "17_17") (pintype "passive"))
    )
    (net (code "221") (name "unconnected-(JP2-Pad18)") (class "Default")
      (node (ref "JP2") (pin "18") (pinfunction "18_18") (pintype "passive"))
    )
    (net (code "222") (name "unconnected-(JP2-Pad19)") (class "Default")
      (node (ref "JP2") (pin "19") (pinfunction "19_19") (pintype "passive"))
    )
    (net (code "223") (name "unconnected-(JP2-Pad20)") (class "Default")
      (node (ref "JP2") (pin "20") (pinfunction "20_20") (pintype "passive"))
    )
    (net (code "224") (name "unconnected-(REG1.2-VOUT2-Pad2)") (class "Default")
      (node (ref "REG1.2") (pin "2") (pinfunction "VOUT2_2") (pintype "bidirectional"))
    )
    (net (code "225") (name "unconnected-(REG2.5-VOUT2-Pad2)") (class "Default")
      (node (ref "REG2.5") (pin "2") (pinfunction "VOUT2_2") (pintype "bidirectional"))
    )
    (net (code "226") (name "unconnected-(U$2-TRI-PadENA)") (class "Default")
      (node (ref "U$2") (pin "ENA") (pinfunction "TRI_ENA") (pintype "input"))
    )
    (net (code "227") (name "unconnected-(U$3-Pad1)") (class "Default")
      (node (ref "U$3") (pin "1") (pinfunction "1_1") (pintype "passive"))
    )
    (net (code "228") (name "unconnected-(U$3-Pad2)") (class "Default")
      (node (ref "U$3") (pin "2") (pinfunction "2_2") (pintype "passive"))
    )
    (net (code "229") (name "unconnected-(U$3-Pad3)") (class "Default")
      (node (ref "U$3") (pin "3") (pinfunction "3_3") (pintype "passive"))
    )
    (net (code "230") (name "unconnected-(U$3-Pad4)") (class "Default")
      (node (ref "U$3") (pin "4") (pinfunction "4_4") (pintype "passive"))
    )
    (net (code "231") (name "unconnected-(U$3-Pad5)") (class "Default")
      (node (ref "U$3") (pin "5") (pinfunction "5_5") (pintype "passive"))
    )
    (net (code "232") (name "unconnected-(U$3-Pad6)") (class "Default")
      (node (ref "U$3") (pin "6") (pinfunction "6_6") (pintype "passive"))
    )
    (net (code "233") (name "unconnected-(U$3-Pad7)") (class "Default")
      (node (ref "U$3") (pin "7") (pinfunction "7_7") (pintype "passive"))
    )
    (net (code "234") (name "unconnected-(U$3-Pad8)") (class "Default")
      (node (ref "U$3") (pin "8") (pinfunction "8_8") (pintype "passive"))
    )
    (net (code "235") (name "unconnected-(U$3-Pad9)") (class "Default")
      (node (ref "U$3") (pin "9") (pinfunction "9_9") (pintype "passive"))
    )
    (net (code "236") (name "unconnected-(U$3-Pad10)") (class "Default")
      (node (ref "U$3") (pin "10") (pinfunction "10_10") (pintype "passive"))
    )
    (net (code "237") (name "unconnected-(U$4-VOUT2-Pad2)") (class "Default")
      (node (ref "U$4") (pin "2") (pinfunction "VOUT2_2") (pintype "bidirectional"))
    )
    (net (code "238") (name "unconnected-(U1A-IO_L27P_0-PadP135)") (class "Default")
      (node (ref "U1") (pin "P135") (pinfunction "IO_L27P_0_P135") (pintype "bidirectional"))
    )
    (net (code "239") (name "unconnected-(U1A-IO_L30N_0-PadP132)") (class "Default")
      (node (ref "U1") (pin "P132") (pinfunction "IO_L30N_0_P132") (pintype "bidirectional"))
    )
    (net (code "240") (name "unconnected-(U1A-IO_L30P_0-PadP131)") (class "Default")
      (node (ref "U1") (pin "P131") (pinfunction "IO_L30P_0_P131") (pintype "bidirectional"))
    )
    (net (code "241") (name "unconnected-(U1A-IO_L31N_0-PadP130)") (class "Default")
      (node (ref "U1") (pin "P130") (pinfunction "IO_L31N_0_P130") (pintype "bidirectional"))
    )
    (net (code "242") (name "unconnected-(U1A-IO_L31P_0VREF_0-PadP129)") (class "Default")
      (node (ref "U1") (pin "P129") (pinfunction "IO_L31P_0VREF_0_P129") (pintype "bidirectional"))
    )
    (net (code "243") (name "unconnected-(U1A-IO_L32N_0GCLK7-PadP128)") (class "Default")
      (node (ref "U1") (pin "P128") (pinfunction "IO_L32N_0GCLK7_P128") (pintype "bidirectional"))
    )
    (net (code "244") (name "unconnected-(U1A-IO_L32P_0GCLK6-PadP127)") (class "Default")
      (node (ref "U1") (pin "P127") (pinfunction "IO_L32P_0GCLK6_P127") (pintype "bidirectional"))
    )
    (net (code "245") (name "unconnected-(U1C-IO-PadP116)") (class "Default")
      (node (ref "U1") (pin "P116") (pinfunction "IO_P116") (pintype "bidirectional"))
    )
    (net (code "246") (name "unconnected-(U1C-IO_L01N_1VRP_1-PadP113)") (class "Default")
      (node (ref "U1") (pin "P113") (pinfunction "IO_L01N_1VRP_1_P113") (pintype "bidirectional"))
    )
    (net (code "247") (name "unconnected-(U1C-IO_L01P_1VRN_1-PadP112)") (class "Default")
      (node (ref "U1") (pin "P112") (pinfunction "IO_L01P_1VRN_1_P112") (pintype "bidirectional"))
    )
    (net (code "248") (name "unconnected-(U1C-IO_L28N_1-PadP119)") (class "Default")
      (node (ref "U1") (pin "P119") (pinfunction "IO_L28N_1_P119") (pintype "bidirectional"))
    )
    (net (code "249") (name "unconnected-(U1C-IO_L28P_1-PadP118)") (class "Default")
      (node (ref "U1") (pin "P118") (pinfunction "IO_L28P_1_P118") (pintype "bidirectional"))
    )
    (net (code "250") (name "unconnected-(U1C-IO_L31N_1VREF_1-PadP123)") (class "Default")
      (node (ref "U1") (pin "P123") (pinfunction "IO_L31N_1VREF_1_P123") (pintype "bidirectional"))
    )
    (net (code "251") (name "unconnected-(U1C-IO_L31P_1-PadP122)") (class "Default")
      (node (ref "U1") (pin "P122") (pinfunction "IO_L31P_1_P122") (pintype "bidirectional"))
    )
    (net (code "252") (name "unconnected-(U1C-IO_L32N_1GCLK5-PadP125)") (class "Default")
      (node (ref "U1") (pin "P125") (pinfunction "IO_L32N_1GCLK5_P125") (pintype "bidirectional"))
    )
    (net (code "253") (name "unconnected-(U1C-IO_L32P_1GCLK4-PadP124)") (class "Default")
      (node (ref "U1") (pin "P124") (pinfunction "IO_L32P_1GCLK4_P124") (pintype "bidirectional"))
    )
    (net (code "254") (name "unconnected-(U1N-HSWAP_EN-PadP142)") (class "Default")
      (node (ref "U1") (pin "P142") (pinfunction "HSWAP_EN_P142") (pintype "bidirectional"))
    )
    (net (code "255") (name "unconnected-(X1-3-Pad2)") (class "Default")
      (node (ref "X1") (pin "2") (pinfunction "3_2") (pintype "passive"))
    )
    (net (code "256") (name "unconnected-(X2-Pad10)") (class "Default")
      (node (ref "X2") (pin "10") (pinfunction "10_10") (pintype "passive"))
    )
    (net (code "257") (name "unconnected-(X2-Pad12)") (class "Default")
      (node (ref "X2") (pin "12") (pinfunction "12_12") (pintype "passive"))
    )
    (net (code "258") (name "unconnected-(X3-Pad2)") (class "Default")
      (node (ref "X3") (pin "2") (pinfunction "2_2") (pintype "passive"))
    )
    (net (code "259") (name "unconnected-(X3-Pad8)") (class "Default")
      (node (ref "X3") (pin "8") (pinfunction "8_8") (pintype "passive"))
    )
    (net (code "260") (name "unconnected-(X4-PadG2)") (class "Default")
      (node (ref "X4") (pin "G2") (pinfunction "G2_G2") (pintype "passive"))
    )
    (net (code "261") (name "unconnected-(X5-PadG2)") (class "Default")
      (node (ref "X5") (pin "G2") (pinfunction "G2_G2") (pintype "passive"))
    )
    (net (code "262") (name "unconnected-(X6-Pad1)") (class "Default")
      (node (ref "X6") (pin "1") (pinfunction "1_1") (pintype "passive"))
    )
  )
)
